# PushButton_RGB_w_Test.net
KiCad netlist of a schematic drawn in EAGLE
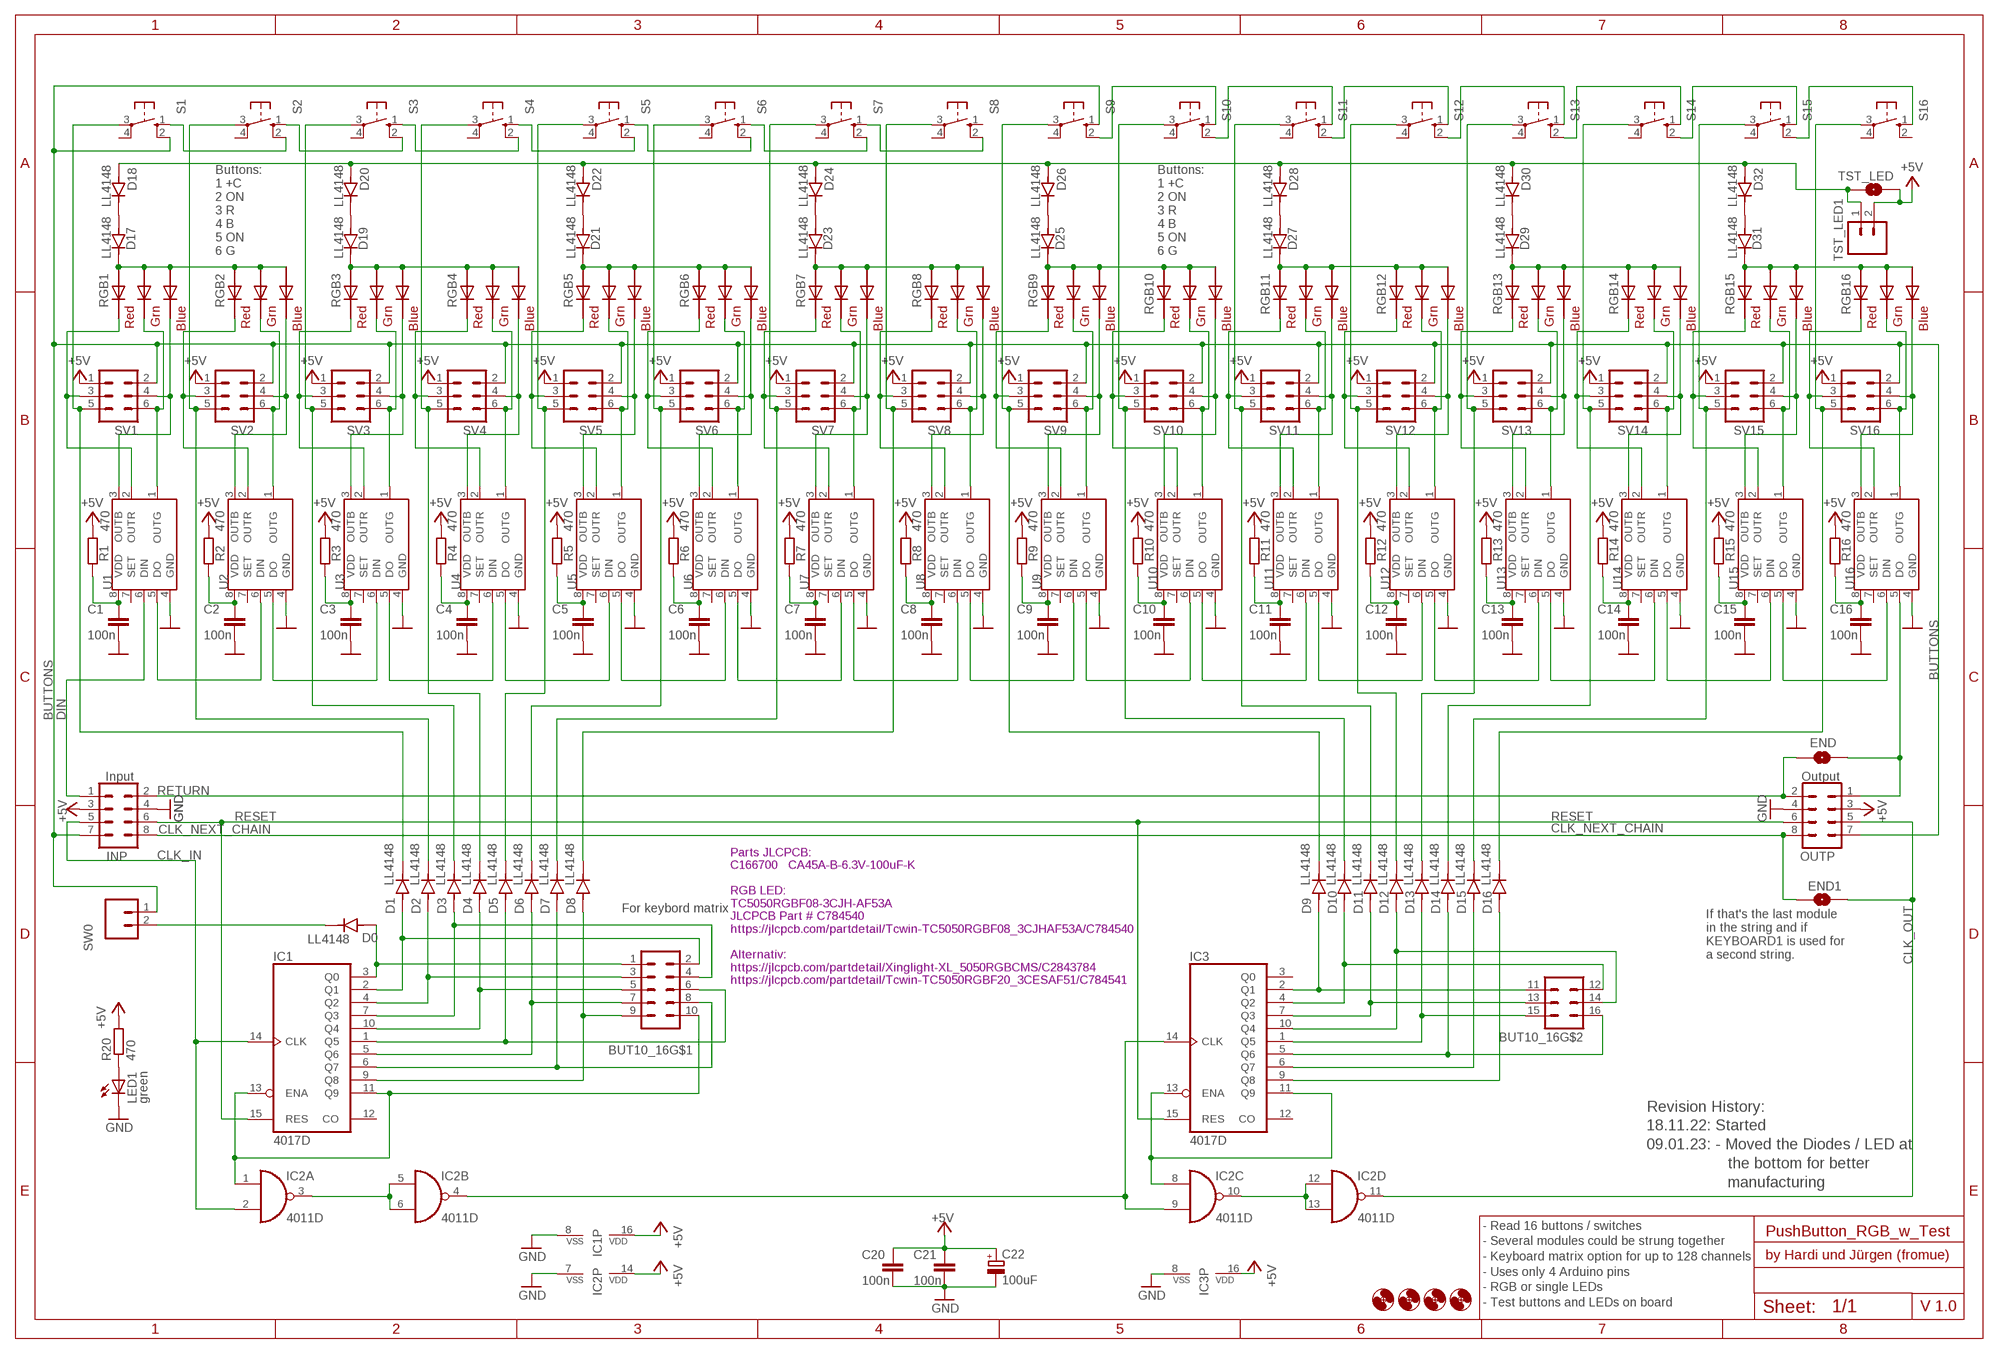
[diagram p0: schematic, sheet 1]

(export (version "E")
  (design (tool "Eeschema 10.0.6"))
  (components
    (comp (ref "BUT10_16")
      (value "CON-HARTING-ML_ML16-2")
      (footprint "eagle-import:CON-HARTING-ML_ML16")
      (libsource (lib "eagle-import") (part "CON-HARTING-ML_ML16-2"))
    )
    (comp (ref "C1")
      (value "100n")
      (footprint "eagle-import:C0603")
      (libsource (lib "eagle-import") (part "C-EUC0603"))
    )
    (comp (ref "C2")
      (value "100n")
      (footprint "eagle-import:C0603")
      (libsource (lib "eagle-import") (part "C-EUC0603"))
    )
    (comp (ref "C3")
      (value "100n")
      (footprint "eagle-import:C0603")
      (libsource (lib "eagle-import") (part "C-EUC0603"))
    )
    (comp (ref "C4")
      (value "100n")
      (footprint "eagle-import:C0603")
      (libsource (lib "eagle-import") (part "C-EUC0603"))
    )
    (comp (ref "C5")
      (value "100n")
      (footprint "eagle-import:C0603")
      (libsource (lib "eagle-import") (part "C-EUC0603"))
    )
    (comp (ref "C6")
      (value "100n")
      (footprint "eagle-import:C0603")
      (libsource (lib "eagle-import") (part "C-EUC0603"))
    )
    (comp (ref "C7")
      (value "100n")
      (footprint "eagle-import:C0603")
      (libsource (lib "eagle-import") (part "C-EUC0603"))
    )
    (comp (ref "C8")
      (value "100n")
      (footprint "eagle-import:C0603")
      (libsource (lib "eagle-import") (part "C-EUC0603"))
    )
    (comp (ref "C9")
      (value "100n")
      (footprint "eagle-import:C0603")
      (libsource (lib "eagle-import") (part "C-EUC0603"))
    )
    (comp (ref "C10")
      (value "100n")
      (footprint "eagle-import:C0603")
      (libsource (lib "eagle-import") (part "C-EUC0603"))
    )
    (comp (ref "C11")
      (value "100n")
      (footprint "eagle-import:C0603")
      (libsource (lib "eagle-import") (part "C-EUC0603"))
    )
    (comp (ref "C12")
      (value "100n")
      (footprint "eagle-import:C0603")
      (libsource (lib "eagle-import") (part "C-EUC0603"))
    )
    (comp (ref "C13")
      (value "100n")
      (footprint "eagle-import:C0603")
      (libsource (lib "eagle-import") (part "C-EUC0603"))
    )
    (comp (ref "C14")
      (value "100n")
      (footprint "eagle-import:C0603")
      (libsource (lib "eagle-import") (part "C-EUC0603"))
    )
    (comp (ref "C15")
      (value "100n")
      (footprint "eagle-import:C0603")
      (libsource (lib "eagle-import") (part "C-EUC0603"))
    )
    (comp (ref "C16")
      (value "100n")
      (footprint "eagle-import:C0603")
      (libsource (lib "eagle-import") (part "C-EUC0603"))
    )
    (comp (ref "C20")
      (value "100n")
      (footprint "eagle-import:C0603")
      (libsource (lib "eagle-import") (part "C-EUC0603"))
    )
    (comp (ref "C21")
      (value "100n")
      (footprint "eagle-import:C0603")
      (libsource (lib "eagle-import") (part "C-EUC0603"))
    )
    (comp (ref "C22")
      (value "100uF")
      (footprint "eagle-import:B_3528-21R")
      (libsource (lib "eagle-import") (part "CPOL-EUB/3528-21R"))
    )
    (comp (ref "D0")
      (value "LL4148")
      (footprint "eagle-import:DIO_LL4148")
      (fields (field (name "MF") "ON"))
      (libsource (lib "eagle-import") (part "LL4148"))
    )
    (comp (ref "D1")
      (value "LL4148")
      (footprint "eagle-import:DIO_LL4148")
      (fields (field (name "MF") "ON"))
      (libsource (lib "eagle-import") (part "LL4148"))
    )
    (comp (ref "D2")
      (value "LL4148")
      (footprint "eagle-import:DIO_LL4148")
      (fields (field (name "MF") "ON"))
      (libsource (lib "eagle-import") (part "LL4148"))
    )
    (comp (ref "D3")
      (value "LL4148")
      (footprint "eagle-import:DIO_LL4148")
      (fields (field (name "MF") "ON"))
      (libsource (lib "eagle-import") (part "LL4148"))
    )
    (comp (ref "D4")
      (value "LL4148")
      (footprint "eagle-import:DIO_LL4148")
      (fields (field (name "MF") "ON"))
      (libsource (lib "eagle-import") (part "LL4148"))
    )
    (comp (ref "D5")
      (value "LL4148")
      (footprint "eagle-import:DIO_LL4148")
      (fields (field (name "MF") "ON"))
      (libsource (lib "eagle-import") (part "LL4148"))
    )
    (comp (ref "D6")
      (value "LL4148")
      (footprint "eagle-import:DIO_LL4148")
      (fields (field (name "MF") "ON"))
      (libsource (lib "eagle-import") (part "LL4148"))
    )
    (comp (ref "D7")
      (value "LL4148")
      (footprint "eagle-import:DIO_LL4148")
      (fields (field (name "MF") "ON"))
      (libsource (lib "eagle-import") (part "LL4148"))
    )
    (comp (ref "D8")
      (value "LL4148")
      (footprint "eagle-import:DIO_LL4148")
      (fields (field (name "MF") "ON"))
      (libsource (lib "eagle-import") (part "LL4148"))
    )
    (comp (ref "D9")
      (value "LL4148")
      (footprint "eagle-import:DIO_LL4148")
      (fields (field (name "MF") "ON"))
      (libsource (lib "eagle-import") (part "LL4148"))
    )
    (comp (ref "D10")
      (value "LL4148")
      (footprint "eagle-import:DIO_LL4148")
      (fields (field (name "MF") "ON"))
      (libsource (lib "eagle-import") (part "LL4148"))
    )
    (comp (ref "D11")
      (value "LL4148")
      (footprint "eagle-import:DIO_LL4148")
      (fields (field (name "MF") "ON"))
      (libsource (lib "eagle-import") (part "LL4148"))
    )
    (comp (ref "D12")
      (value "LL4148")
      (footprint "eagle-import:DIO_LL4148")
      (fields (field (name "MF") "ON"))
      (libsource (lib "eagle-import") (part "LL4148"))
    )
    (comp (ref "D13")
      (value "LL4148")
      (footprint "eagle-import:DIO_LL4148")
      (fields (field (name "MF") "ON"))
      (libsource (lib "eagle-import") (part "LL4148"))
    )
    (comp (ref "D14")
      (value "LL4148")
      (footprint "eagle-import:DIO_LL4148")
      (fields (field (name "MF") "ON"))
      (libsource (lib "eagle-import") (part "LL4148"))
    )
    (comp (ref "D15")
      (value "LL4148")
      (footprint "eagle-import:DIO_LL4148")
      (fields (field (name "MF") "ON"))
      (libsource (lib "eagle-import") (part "LL4148"))
    )
    (comp (ref "D16")
      (value "LL4148")
      (footprint "eagle-import:DIO_LL4148")
      (fields (field (name "MF") "ON"))
      (libsource (lib "eagle-import") (part "LL4148"))
    )
    (comp (ref "D17")
      (value "LL4148")
      (footprint "eagle-import:DIO_LL4148")
      (fields (field (name "MF") "ON"))
      (libsource (lib "eagle-import") (part "LL4148"))
    )
    (comp (ref "D18")
      (value "LL4148")
      (footprint "eagle-import:DIO_LL4148")
      (fields (field (name "MF") "ON"))
      (libsource (lib "eagle-import") (part "LL4148"))
    )
    (comp (ref "D19")
      (value "LL4148")
      (footprint "eagle-import:DIO_LL4148")
      (fields (field (name "MF") "ON"))
      (libsource (lib "eagle-import") (part "LL4148"))
    )
    (comp (ref "D20")
      (value "LL4148")
      (footprint "eagle-import:DIO_LL4148")
      (fields (field (name "MF") "ON"))
      (libsource (lib "eagle-import") (part "LL4148"))
    )
    (comp (ref "D21")
      (value "LL4148")
      (footprint "eagle-import:DIO_LL4148")
      (fields (field (name "MF") "ON"))
      (libsource (lib "eagle-import") (part "LL4148"))
    )
    (comp (ref "D22")
      (value "LL4148")
      (footprint "eagle-import:DIO_LL4148")
      (fields (field (name "MF") "ON"))
      (libsource (lib "eagle-import") (part "LL4148"))
    )
    (comp (ref "D23")
      (value "LL4148")
      (footprint "eagle-import:DIO_LL4148")
      (fields (field (name "MF") "ON"))
      (libsource (lib "eagle-import") (part "LL4148"))
    )
    (comp (ref "D24")
      (value "LL4148")
      (footprint "eagle-import:DIO_LL4148")
      (fields (field (name "MF") "ON"))
      (libsource (lib "eagle-import") (part "LL4148"))
    )
    (comp (ref "D25")
      (value "LL4148")
      (footprint "eagle-import:DIO_LL4148")
      (fields (field (name "MF") "ON"))
      (libsource (lib "eagle-import") (part "LL4148"))
    )
    (comp (ref "D26")
      (value "LL4148")
      (footprint "eagle-import:DIO_LL4148")
      (fields (field (name "MF") "ON"))
      (libsource (lib "eagle-import") (part "LL4148"))
    )
    (comp (ref "D27")
      (value "LL4148")
      (footprint "eagle-import:DIO_LL4148")
      (fields (field (name "MF") "ON"))
      (libsource (lib "eagle-import") (part "LL4148"))
    )
    (comp (ref "D28")
      (value "LL4148")
      (footprint "eagle-import:DIO_LL4148")
      (fields (field (name "MF") "ON"))
      (libsource (lib "eagle-import") (part "LL4148"))
    )
    (comp (ref "D29")
      (value "LL4148")
      (footprint "eagle-import:DIO_LL4148")
      (fields (field (name "MF") "ON"))
      (libsource (lib "eagle-import") (part "LL4148"))
    )
    (comp (ref "D30")
      (value "LL4148")
      (footprint "eagle-import:DIO_LL4148")
      (fields (field (name "MF") "ON"))
      (libsource (lib "eagle-import") (part "LL4148"))
    )
    (comp (ref "D31")
      (value "LL4148")
      (footprint "eagle-import:DIO_LL4148")
      (fields (field (name "MF") "ON"))
      (libsource (lib "eagle-import") (part "LL4148"))
    )
    (comp (ref "D32")
      (value "LL4148")
      (footprint "eagle-import:DIO_LL4148")
      (fields (field (name "MF") "ON"))
      (libsource (lib "eagle-import") (part "LL4148"))
    )
    (comp (ref "END")
      (value "SOLDERJUMPERNO")
      (footprint "eagle-import:SJ_2S-NO")
      (libsource (lib "eagle-import") (part "SOLDERJUMPERNO"))
    )
    (comp (ref "END1")
      (value "SOLDERJUMPERNO")
      (footprint "eagle-import:SJ_2S-NO")
      (libsource (lib "eagle-import") (part "SOLDERJUMPERNO"))
    )
    (comp (ref "H1")
      (value "MOUNT-HOLE3.0")
      (footprint "eagle-import:3,0")
      (libsource (lib "eagle-import") (part "MOUNT-HOLE3.0"))
    )
    (comp (ref "H2")
      (value "MOUNT-HOLE3.0")
      (footprint "eagle-import:3,0")
      (libsource (lib "eagle-import") (part "MOUNT-HOLE3.0"))
    )
    (comp (ref "H3")
      (value "MOUNT-HOLE3.0")
      (footprint "eagle-import:3,0")
      (libsource (lib "eagle-import") (part "MOUNT-HOLE3.0"))
    )
    (comp (ref "H4")
      (value "MOUNT-HOLE3.0")
      (footprint "eagle-import:3,0")
      (libsource (lib "eagle-import") (part "MOUNT-HOLE3.0"))
    )
    (comp (ref "IC1")
      (value "4017D")
      (footprint "eagle-import:SO16")
      (libsource (lib "eagle-import") (part "4017D"))
    )
    (comp (ref "IC2")
      (value "4011D")
      (footprint "eagle-import:SO14")
      (fields (field (name "SPICEPREFIX") "J"))
      (libsource (lib "eagle-import") (part "4011D"))
    )
    (comp (ref "IC3")
      (value "4017D")
      (footprint "eagle-import:SO16")
      (libsource (lib "eagle-import") (part "4017D"))
    )
    (comp (ref "INP")
      (value "CON-HARTING-ML_ML08")
      (footprint "eagle-import:CON-HARTING-ML_ML08")
      (libsource (lib "eagle-import") (part "CON-HARTING-ML_ML08"))
    )
    (comp (ref "LED1")
      (value "green")
      (footprint "eagle-import:CHIPLED_0805")
      (libsource (lib "eagle-import") (part "LEDCHIPLED_0805"))
    )
    (comp (ref "OUTP")
      (value "CON-HARTING-ML_ML08")
      (footprint "eagle-import:CON-HARTING-ML_ML08")
      (libsource (lib "eagle-import") (part "CON-HARTING-ML_ML08"))
    )
    (comp (ref "R1")
      (value "470")
      (footprint "eagle-import:R0603")
      (libsource (lib "eagle-import") (part "R-EU_R0603"))
    )
    (comp (ref "R2")
      (value "470")
      (footprint "eagle-import:R0603")
      (libsource (lib "eagle-import") (part "R-EU_R0603"))
    )
    (comp (ref "R3")
      (value "470")
      (footprint "eagle-import:R0603")
      (libsource (lib "eagle-import") (part "R-EU_R0603"))
    )
    (comp (ref "R4")
      (value "470")
      (footprint "eagle-import:R0603")
      (libsource (lib "eagle-import") (part "R-EU_R0603"))
    )
    (comp (ref "R5")
      (value "470")
      (footprint "eagle-import:R0603")
      (libsource (lib "eagle-import") (part "R-EU_R0603"))
    )
    (comp (ref "R6")
      (value "470")
      (footprint "eagle-import:R0603")
      (libsource (lib "eagle-import") (part "R-EU_R0603"))
    )
    (comp (ref "R7")
      (value "470")
      (footprint "eagle-import:R0603")
      (libsource (lib "eagle-import") (part "R-EU_R0603"))
    )
    (comp (ref "R8")
      (value "470")
      (footprint "eagle-import:R0603")
      (libsource (lib "eagle-import") (part "R-EU_R0603"))
    )
    (comp (ref "R9")
      (value "470")
      (footprint "eagle-import:R0603")
      (libsource (lib "eagle-import") (part "R-EU_R0603"))
    )
    (comp (ref "R10")
      (value "470")
      (footprint "eagle-import:R0603")
      (libsource (lib "eagle-import") (part "R-EU_R0603"))
    )
    (comp (ref "R11")
      (value "470")
      (footprint "eagle-import:R0603")
      (libsource (lib "eagle-import") (part "R-EU_R0603"))
    )
    (comp (ref "R12")
      (value "470")
      (footprint "eagle-import:R0603")
      (libsource (lib "eagle-import") (part "R-EU_R0603"))
    )
    (comp (ref "R13")
      (value "470")
      (footprint "eagle-import:R0603")
      (libsource (lib "eagle-import") (part "R-EU_R0603"))
    )
    (comp (ref "R14")
      (value "470")
      (footprint "eagle-import:R0603")
      (libsource (lib "eagle-import") (part "R-EU_R0603"))
    )
    (comp (ref "R15")
      (value "470")
      (footprint "eagle-import:R0603")
      (libsource (lib "eagle-import") (part "R-EU_R0603"))
    )
    (comp (ref "R16")
      (value "470")
      (footprint "eagle-import:R0603")
      (libsource (lib "eagle-import") (part "R-EU_R0603"))
    )
    (comp (ref "R20")
      (value "470")
      (footprint "eagle-import:R0603")
      (libsource (lib "eagle-import") (part "R-EU_R0603"))
    )
    (comp (ref "RGB1")
      (value "RGBLED5050")
      (footprint "eagle-import:RGBLED5050")
      (libsource (lib "eagle-import") (part "RGBLED5050"))
    )
    (comp (ref "RGB2")
      (value "RGBLED5050")
      (footprint "eagle-import:RGBLED5050")
      (libsource (lib "eagle-import") (part "RGBLED5050"))
    )
    (comp (ref "RGB3")
      (value "RGBLED5050")
      (footprint "eagle-import:RGBLED5050")
      (libsource (lib "eagle-import") (part "RGBLED5050"))
    )
    (comp (ref "RGB4")
      (value "RGBLED5050")
      (footprint "eagle-import:RGBLED5050")
      (libsource (lib "eagle-import") (part "RGBLED5050"))
    )
    (comp (ref "RGB5")
      (value "RGBLED5050")
      (footprint "eagle-import:RGBLED5050")
      (libsource (lib "eagle-import") (part "RGBLED5050"))
    )
    (comp (ref "RGB6")
      (value "RGBLED5050")
      (footprint "eagle-import:RGBLED5050")
      (libsource (lib "eagle-import") (part "RGBLED5050"))
    )
    (comp (ref "RGB7")
      (value "RGBLED5050")
      (footprint "eagle-import:RGBLED5050")
      (libsource (lib "eagle-import") (part "RGBLED5050"))
    )
    (comp (ref "RGB8")
      (value "RGBLED5050")
      (footprint "eagle-import:RGBLED5050")
      (libsource (lib "eagle-import") (part "RGBLED5050"))
    )
    (comp (ref "RGB9")
      (value "RGBLED5050")
      (footprint "eagle-import:RGBLED5050")
      (libsource (lib "eagle-import") (part "RGBLED5050"))
    )
    (comp (ref "RGB10")
      (value "RGBLED5050")
      (footprint "eagle-import:RGBLED5050")
      (libsource (lib "eagle-import") (part "RGBLED5050"))
    )
    (comp (ref "RGB11")
      (value "RGBLED5050")
      (footprint "eagle-import:RGBLED5050")
      (libsource (lib "eagle-import") (part "RGBLED5050"))
    )
    (comp (ref "RGB12")
      (value "RGBLED5050")
      (footprint "eagle-import:RGBLED5050")
      (libsource (lib "eagle-import") (part "RGBLED5050"))
    )
    (comp (ref "RGB13")
      (value "RGBLED5050")
      (footprint "eagle-import:RGBLED5050")
      (libsource (lib "eagle-import") (part "RGBLED5050"))
    )
    (comp (ref "RGB14")
      (value "RGBLED5050")
      (footprint "eagle-import:RGBLED5050")
      (libsource (lib "eagle-import") (part "RGBLED5050"))
    )
    (comp (ref "RGB15")
      (value "RGBLED5050")
      (footprint "eagle-import:RGBLED5050")
      (libsource (lib "eagle-import") (part "RGBLED5050"))
    )
    (comp (ref "RGB16")
      (value "RGBLED5050")
      (footprint "eagle-import:RGBLED5050")
      (libsource (lib "eagle-import") (part "RGBLED5050"))
    )
    (comp (ref "S1")
      (value "10-XXB3F-10XX_SMD")
      (footprint "eagle-import:B3F-10XX_SMD")
      (libsource (lib "eagle-import") (part "10-XXB3F-10XX_SMD"))
    )
    (comp (ref "S2")
      (value "10-XXB3F-10XX_SMD")
      (footprint "eagle-import:B3F-10XX_SMD")
      (libsource (lib "eagle-import") (part "10-XXB3F-10XX_SMD"))
    )
    (comp (ref "S3")
      (value "10-XXB3F-10XX_SMD")
      (footprint "eagle-import:B3F-10XX_SMD")
      (libsource (lib "eagle-import") (part "10-XXB3F-10XX_SMD"))
    )
    (comp (ref "S4")
      (value "10-XXB3F-10XX_SMD")
      (footprint "eagle-import:B3F-10XX_SMD")
      (libsource (lib "eagle-import") (part "10-XXB3F-10XX_SMD"))
    )
    (comp (ref "S5")
      (value "10-XXB3F-10XX_SMD")
      (footprint "eagle-import:B3F-10XX_SMD")
      (libsource (lib "eagle-import") (part "10-XXB3F-10XX_SMD"))
    )
    (comp (ref "S6")
      (value "10-XXB3F-10XX_SMD")
      (footprint "eagle-import:B3F-10XX_SMD")
      (libsource (lib "eagle-import") (part "10-XXB3F-10XX_SMD"))
    )
    (comp (ref "S7")
      (value "10-XXB3F-10XX_SMD")
      (footprint "eagle-import:B3F-10XX_SMD")
      (libsource (lib "eagle-import") (part "10-XXB3F-10XX_SMD"))
    )
    (comp (ref "S8")
      (value "10-XXB3F-10XX_SMD")
      (footprint "eagle-import:B3F-10XX_SMD")
      (libsource (lib "eagle-import") (part "10-XXB3F-10XX_SMD"))
    )
    (comp (ref "S9")
      (value "10-XXB3F-10XX_SMD")
      (footprint "eagle-import:B3F-10XX_SMD")
      (libsource (lib "eagle-import") (part "10-XXB3F-10XX_SMD"))
    )
    (comp (ref "S10")
      (value "10-XXB3F-10XX_SMD")
      (footprint "eagle-import:B3F-10XX_SMD")
      (libsource (lib "eagle-import") (part "10-XXB3F-10XX_SMD"))
    )
    (comp (ref "S11")
      (value "10-XXB3F-10XX_SMD")
      (footprint "eagle-import:B3F-10XX_SMD")
      (libsource (lib "eagle-import") (part "10-XXB3F-10XX_SMD"))
    )
    (comp (ref "S12")
      (value "10-XXB3F-10XX_SMD")
      (footprint "eagle-import:B3F-10XX_SMD")
      (libsource (lib "eagle-import") (part "10-XXB3F-10XX_SMD"))
    )
    (comp (ref "S13")
      (value "10-XXB3F-10XX_SMD")
      (footprint "eagle-import:B3F-10XX_SMD")
      (libsource (lib "eagle-import") (part "10-XXB3F-10XX_SMD"))
    )
    (comp (ref "S14")
      (value "10-XXB3F-10XX_SMD")
      (footprint "eagle-import:B3F-10XX_SMD")
      (libsource (lib "eagle-import") (part "10-XXB3F-10XX_SMD"))
    )
    (comp (ref "S15")
      (value "10-XXB3F-10XX_SMD")
      (footprint "eagle-import:B3F-10XX_SMD")
      (libsource (lib "eagle-import") (part "10-XXB3F-10XX_SMD"))
    )
    (comp (ref "S16")
      (value "10-XXB3F-10XX_SMD")
      (footprint "eagle-import:B3F-10XX_SMD")
      (libsource (lib "eagle-import") (part "10-XXB3F-10XX_SMD"))
    )
    (comp (ref "SV1")
      (value "CON-HARTING-ML_ML6")
      (footprint "eagle-import:CON-HARTING-ML_ML6")
      (libsource (lib "eagle-import") (part "CON-HARTING-ML_ML6"))
    )
    (comp (ref "SV2")
      (value "CON-HARTING-ML_ML6")
      (footprint "eagle-import:CON-HARTING-ML_ML6")
      (libsource (lib "eagle-import") (part "CON-HARTING-ML_ML6"))
    )
    (comp (ref "SV3")
      (value "CON-HARTING-ML_ML6")
      (footprint "eagle-import:CON-HARTING-ML_ML6")
      (libsource (lib "eagle-import") (part "CON-HARTING-ML_ML6"))
    )
    (comp (ref "SV4")
      (value "CON-HARTING-ML_ML6")
      (footprint "eagle-import:CON-HARTING-ML_ML6")
      (libsource (lib "eagle-import") (part "CON-HARTING-ML_ML6"))
    )
    (comp (ref "SV5")
      (value "CON-HARTING-ML_ML6")
      (footprint "eagle-import:CON-HARTING-ML_ML6")
      (libsource (lib "eagle-import") (part "CON-HARTING-ML_ML6"))
    )
    (comp (ref "SV6")
      (value "CON-HARTING-ML_ML6")
      (footprint "eagle-import:CON-HARTING-ML_ML6")
      (libsource (lib "eagle-import") (part "CON-HARTING-ML_ML6"))
    )
    (comp (ref "SV7")
      (value "CON-HARTING-ML_ML6")
      (footprint "eagle-import:CON-HARTING-ML_ML6")
      (libsource (lib "eagle-import") (part "CON-HARTING-ML_ML6"))
    )
    (comp (ref "SV8")
      (value "CON-HARTING-ML_ML6")
      (footprint "eagle-import:CON-HARTING-ML_ML6")
      (libsource (lib "eagle-import") (part "CON-HARTING-ML_ML6"))
    )
    (comp (ref "SV9")
      (value "CON-HARTING-ML_ML6")
      (footprint "eagle-import:CON-HARTING-ML_ML6")
      (libsource (lib "eagle-import") (part "CON-HARTING-ML_ML6"))
    )
    (comp (ref "SV10")
      (value "CON-HARTING-ML_ML6")
      (footprint "eagle-import:CON-HARTING-ML_ML6")
      (libsource (lib "eagle-import") (part "CON-HARTING-ML_ML6"))
    )
    (comp (ref "SV11")
      (value "CON-HARTING-ML_ML6")
      (footprint "eagle-import:CON-HARTING-ML_ML6")
      (libsource (lib "eagle-import") (part "CON-HARTING-ML_ML6"))
    )
    (comp (ref "SV12")
      (value "CON-HARTING-ML_ML6")
      (footprint "eagle-import:CON-HARTING-ML_ML6")
      (libsource (lib "eagle-import") (part "CON-HARTING-ML_ML6"))
    )
    (comp (ref "SV13")
      (value "CON-HARTING-ML_ML6")
      (footprint "eagle-import:CON-HARTING-ML_ML6")
      (libsource (lib "eagle-import") (part "CON-HARTING-ML_ML6"))
    )
    (comp (ref "SV14")
      (value "CON-HARTING-ML_ML6")
      (footprint "eagle-import:CON-HARTING-ML_ML6")
      (libsource (lib "eagle-import") (part "CON-HARTING-ML_ML6"))
    )
    (comp (ref "SV15")
      (value "CON-HARTING-ML_ML6")
      (footprint "eagle-import:CON-HARTING-ML_ML6")
      (libsource (lib "eagle-import") (part "CON-HARTING-ML_ML6"))
    )
    (comp (ref "SV16")
      (value "CON-HARTING-ML_ML6")
      (footprint "eagle-import:CON-HARTING-ML_ML6")
      (libsource (lib "eagle-import") (part "CON-HARTING-ML_ML6"))
    )
    (comp (ref "SW0")
      (value "M02PTH")
      (footprint "eagle-import:1X02")
      (libsource (lib "eagle-import") (part "M02PTH"))
    )
    (comp (ref "TST_LED")
      (value "SOLDERJUMPERNO")
      (footprint "eagle-import:SJ_2S-NO")
      (libsource (lib "eagle-import") (part "SOLDERJUMPERNO"))
    )
    (comp (ref "TST_LED1")
      (value "Tst_LED")
      (footprint "eagle-import:1X02")
      (libsource (lib "eagle-import") (part "M02PTH"))
    )
    (comp (ref "U1")
      (value "S3PO_MODUL_WS2811_SOUND_MP3-TF-16P_WS2811_AND_ATTINY_WS2811-ICSOP8")
      (footprint "eagle-import:SOP8")
      (libsource (lib "eagle-import") (part "S3PO_MODUL_WS2811_SOUND_MP3-TF-16P_WS2811_AND_ATTINY_WS2811-ICSOP8"))
    )
    (comp (ref "U2")
      (value "S3PO_MODUL_WS2811_SOUND_MP3-TF-16P_WS2811_AND_ATTINY_WS2811-ICSOP8")
      (footprint "eagle-import:SOP8")
      (libsource (lib "eagle-import") (part "S3PO_MODUL_WS2811_SOUND_MP3-TF-16P_WS2811_AND_ATTINY_WS2811-ICSOP8"))
    )
    (comp (ref "U3")
      (value "S3PO_MODUL_WS2811_SOUND_MP3-TF-16P_WS2811_AND_ATTINY_WS2811-ICSOP8")
      (footprint "eagle-import:SOP8")
      (libsource (lib "eagle-import") (part "S3PO_MODUL_WS2811_SOUND_MP3-TF-16P_WS2811_AND_ATTINY_WS2811-ICSOP8"))
    )
    (comp (ref "U4")
      (value "S3PO_MODUL_WS2811_SOUND_MP3-TF-16P_WS2811_AND_ATTINY_WS2811-ICSOP8")
      (footprint "eagle-import:SOP8")
      (libsource (lib "eagle-import") (part "S3PO_MODUL_WS2811_SOUND_MP3-TF-16P_WS2811_AND_ATTINY_WS2811-ICSOP8"))
    )
    (comp (ref "U5")
      (value "S3PO_MODUL_WS2811_SOUND_MP3-TF-16P_WS2811_AND_ATTINY_WS2811-ICSOP8")
      (footprint "eagle-import:SOP8")
      (libsource (lib "eagle-import") (part "S3PO_MODUL_WS2811_SOUND_MP3-TF-16P_WS2811_AND_ATTINY_WS2811-ICSOP8"))
    )
    (comp (ref "U6")
      (value "S3PO_MODUL_WS2811_SOUND_MP3-TF-16P_WS2811_AND_ATTINY_WS2811-ICSOP8")
      (footprint "eagle-import:SOP8")
      (libsource (lib "eagle-import") (part "S3PO_MODUL_WS2811_SOUND_MP3-TF-16P_WS2811_AND_ATTINY_WS2811-ICSOP8"))
    )
    (comp (ref "U7")
      (value "S3PO_MODUL_WS2811_SOUND_MP3-TF-16P_WS2811_AND_ATTINY_WS2811-ICSOP8")
      (footprint "eagle-import:SOP8")
      (libsource (lib "eagle-import") (part "S3PO_MODUL_WS2811_SOUND_MP3-TF-16P_WS2811_AND_ATTINY_WS2811-ICSOP8"))
    )
    (comp (ref "U8")
      (value "S3PO_MODUL_WS2811_SOUND_MP3-TF-16P_WS2811_AND_ATTINY_WS2811-ICSOP8")
      (footprint "eagle-import:SOP8")
      (libsource (lib "eagle-import") (part "S3PO_MODUL_WS2811_SOUND_MP3-TF-16P_WS2811_AND_ATTINY_WS2811-ICSOP8"))
    )
    (comp (ref "U9")
      (value "S3PO_MODUL_WS2811_SOUND_MP3-TF-16P_WS2811_AND_ATTINY_WS2811-ICSOP8")
      (footprint "eagle-import:SOP8")
      (libsource (lib "eagle-import") (part "S3PO_MODUL_WS2811_SOUND_MP3-TF-16P_WS2811_AND_ATTINY_WS2811-ICSOP8"))
    )
    (comp (ref "U10")
      (value "S3PO_MODUL_WS2811_SOUND_MP3-TF-16P_WS2811_AND_ATTINY_WS2811-ICSOP8")
      (footprint "eagle-import:SOP8")
      (libsource (lib "eagle-import") (part "S3PO_MODUL_WS2811_SOUND_MP3-TF-16P_WS2811_AND_ATTINY_WS2811-ICSOP8"))
    )
    (comp (ref "U11")
      (value "S3PO_MODUL_WS2811_SOUND_MP3-TF-16P_WS2811_AND_ATTINY_WS2811-ICSOP8")
      (footprint "eagle-import:SOP8")
      (libsource (lib "eagle-import") (part "S3PO_MODUL_WS2811_SOUND_MP3-TF-16P_WS2811_AND_ATTINY_WS2811-ICSOP8"))
    )
    (comp (ref "U12")
      (value "S3PO_MODUL_WS2811_SOUND_MP3-TF-16P_WS2811_AND_ATTINY_WS2811-ICSOP8")
      (footprint "eagle-import:SOP8")
      (libsource (lib "eagle-import") (part "S3PO_MODUL_WS2811_SOUND_MP3-TF-16P_WS2811_AND_ATTINY_WS2811-ICSOP8"))
    )
    (comp (ref "U13")
      (value "S3PO_MODUL_WS2811_SOUND_MP3-TF-16P_WS2811_AND_ATTINY_WS2811-ICSOP8")
      (footprint "eagle-import:SOP8")
      (libsource (lib "eagle-import") (part "S3PO_MODUL_WS2811_SOUND_MP3-TF-16P_WS2811_AND_ATTINY_WS2811-ICSOP8"))
    )
    (comp (ref "U14")
      (value "S3PO_MODUL_WS2811_SOUND_MP3-TF-16P_WS2811_AND_ATTINY_WS2811-ICSOP8")
      (footprint "eagle-import:SOP8")
      (libsource (lib "eagle-import") (part "S3PO_MODUL_WS2811_SOUND_MP3-TF-16P_WS2811_AND_ATTINY_WS2811-ICSOP8"))
    )
    (comp (ref "U15")
      (value "S3PO_MODUL_WS2811_SOUND_MP3-TF-16P_WS2811_AND_ATTINY_WS2811-ICSOP8")
      (footprint "eagle-import:SOP8")
      (libsource (lib "eagle-import") (part "S3PO_MODUL_WS2811_SOUND_MP3-TF-16P_WS2811_AND_ATTINY_WS2811-ICSOP8"))
    )
    (comp (ref "U16")
      (value "S3PO_MODUL_WS2811_SOUND_MP3-TF-16P_WS2811_AND_ATTINY_WS2811-ICSOP8")
      (footprint "eagle-import:SOP8")
      (libsource (lib "eagle-import") (part "S3PO_MODUL_WS2811_SOUND_MP3-TF-16P_WS2811_AND_ATTINY_WS2811-ICSOP8"))
    )
  )
  (nets
    (net (code "1") (name "+5V") (class "Default")
      (node (ref "C20") (pin "1") (pinfunction "1_1") (pintype "passive"))
      (node (ref "C21") (pin "1") (pinfunction "1_1") (pintype "passive"))
      (node (ref "C22") (pin "+") (pinfunction "+_+") (pintype "passive"))
      (node (ref "IC1") (pin "16") (pinfunction "VDD_16") (pintype "power_in"))
      (node (ref "IC2") (pin "14") (pinfunction "VDD_14") (pintype "power_in"))
      (node (ref "IC3") (pin "16") (pinfunction "VDD_16") (pintype "power_in"))
      (node (ref "INP") (pin "3") (pinfunction "3_3") (pintype "passive"))
      (node (ref "OUTP") (pin "3") (pinfunction "3_3") (pintype "passive"))
      (node (ref "R1") (pin "2") (pinfunction "2_2") (pintype "passive"))
      (node (ref "R10") (pin "2") (pinfunction "2_2") (pintype "passive"))
      (node (ref "R11") (pin "2") (pinfunction "2_2") (pintype "passive"))
      (node (ref "R12") (pin "2") (pinfunction "2_2") (pintype "passive"))
      (node (ref "R13") (pin "2") (pinfunction "2_2") (pintype "passive"))
      (node (ref "R14") (pin "2") (pinfunction "2_2") (pintype "passive"))
      (node (ref "R15") (pin "2") (pinfunction "2_2") (pintype "passive"))
      (node (ref "R16") (pin "2") (pinfunction "2_2") (pintype "passive"))
      (node (ref "R2") (pin "2") (pinfunction "2_2") (pintype "passive"))
      (node (ref "R20") (pin "2") (pinfunction "2_2") (pintype "passive"))
      (node (ref "R3") (pin "2") (pinfunction "2_2") (pintype "passive"))
      (node (ref "R4") (pin "2") (pinfunction "2_2") (pintype "passive"))
      (node (ref "R5") (pin "2") (pinfunction "2_2") (pintype "passive"))
      (node (ref "R6") (pin "2") (pinfunction "2_2") (pintype "passive"))
      (node (ref "R7") (pin "2") (pinfunction "2_2") (pintype "passive"))
      (node (ref "R8") (pin "2") (pinfunction "2_2") (pintype "passive"))
      (node (ref "R9") (pin "2") (pinfunction "2_2") (pintype "passive"))
      (node (ref "SV1") (pin "1") (pinfunction "1_1") (pintype "passive"))
      (node (ref "SV10") (pin "1") (pinfunction "1_1") (pintype "passive"))
      (node (ref "SV11") (pin "1") (pinfunction "1_1") (pintype "passive"))
      (node (ref "SV12") (pin "1") (pinfunction "1_1") (pintype "passive"))
      (node (ref "SV13") (pin "1") (pinfunction "1_1") (pintype "passive"))
      (node (ref "SV14") (pin "1") (pinfunction "1_1") (pintype "passive"))
      (node (ref "SV15") (pin "1") (pinfunction "1_1") (pintype "passive"))
      (node (ref "SV16") (pin "1") (pinfunction "1_1") (pintype "passive"))
      (node (ref "SV2") (pin "1") (pinfunction "1_1") (pintype "passive"))
      (node (ref "SV3") (pin "1") (pinfunction "1_1") (pintype "passive"))
      (node (ref "SV4") (pin "1") (pinfunction "1_1") (pintype "passive"))
      (node (ref "SV5") (pin "1") (pinfunction "1_1") (pintype "passive"))
      (node (ref "SV6") (pin "1") (pinfunction "1_1") (pintype "passive"))
      (node (ref "SV7") (pin "1") (pinfunction "1_1") (pintype "passive"))
      (node (ref "SV8") (pin "1") (pinfunction "1_1") (pintype "passive"))
      (node (ref "SV9") (pin "1") (pinfunction "1_1") (pintype "passive"))
      (node (ref "TST_LED") (pin "1") (pinfunction "1_1") (pintype "passive"))
      (node (ref "TST_LED1") (pin "2") (pinfunction "2_2") (pintype "passive"))
    )
    (net (code "2") (name "/BUTTONS") (class "Default")
      (node (ref "INP") (pin "7") (pinfunction "7_7") (pintype "passive"))
      (node (ref "OUTP") (pin "7") (pinfunction "7_7") (pintype "passive"))
      (node (ref "S1") (pin "2") (pinfunction "S1_2") (pintype "passive"))
      (node (ref "S9") (pin "1") (pinfunction "S_1") (pintype "passive"))
      (node (ref "SV1") (pin "2") (pinfunction "2_2") (pintype "passive"))
      (node (ref "SV10") (pin "2") (pinfunction "2_2") (pintype "passive"))
      (node (ref "SV11") (pin "2") (pinfunction "2_2") (pintype "passive"))
      (node (ref "SV12") (pin "2") (pinfunction "2_2") (pintype "passive"))
      (node (ref "SV13") (pin "2") (pinfunction "2_2") (pintype "passive"))
      (node (ref "SV14") (pin "2") (pinfunction "2_2") (pintype "passive"))
      (node (ref "SV15") (pin "2") (pinfunction "2_2") (pintype "passive"))
      (node (ref "SV16") (pin "2") (pinfunction "2_2") (pintype "passive"))
      (node (ref "SV2") (pin "2") (pinfunction "2_2") (pintype "passive"))
      (node (ref "SV3") (pin "2") (pinfunction "2_2") (pintype "passive"))
      (node (ref "SV4") (pin "2") (pinfunction "2_2") (pintype "passive"))
      (node (ref "SV5") (pin "2") (pinfunction "2_2") (pintype "passive"))
      (node (ref "SV6") (pin "2") (pinfunction "2_2") (pintype "passive"))
      (node (ref "SV7") (pin "2") (pinfunction "2_2") (pintype "passive"))
      (node (ref "SV8") (pin "2") (pinfunction "2_2") (pintype "passive"))
      (node (ref "SV9") (pin "2") (pinfunction "2_2") (pintype "passive"))
      (node (ref "SW0") (pin "1") (pinfunction "1_1") (pintype "passive"))
    )
    (net (code "3") (name "/CLK_IN") (class "Default")
      (node (ref "IC1") (pin "14") (pinfunction "CLK_14") (pintype "input"))
      (node (ref "IC2") (pin "2") (pinfunction "I1_2") (pintype "input"))
      (node (ref "INP") (pin "5") (pinfunction "5_5") (pintype "passive"))
    )
    (net (code "4") (name "/CLK_NEXT_CHAIN") (class "Default")
      (node (ref "END1") (pin "2") (pinfunction "2_2") (pintype "passive"))
      (node (ref "INP") (pin "8") (pinfunction "8_8") (pintype "passive"))
      (node (ref "OUTP") (pin "8") (pinfunction "8_8") (pintype "passive"))
    )
    (net (code "5") (name "/CLK_OUT") (class "Default")
      (node (ref "END1") (pin "1") (pinfunction "1_1") (pintype "passive"))
      (node (ref "IC2") (pin "11") (pinfunction "O_11") (pintype "output"))
      (node (ref "OUTP") (pin "5") (pinfunction "5_5") (pintype "passive"))
    )
    (net (code "6") (name "/DIN") (class "Default")
      (node (ref "INP") (pin "1") (pinfunction "1_1") (pintype "passive"))
      (node (ref "U1") (pin "6") (pinfunction "DIN_6") (pintype "input"))
    )
    (net (code "7") (name "/RESET") (class "Default")
      (node (ref "IC1") (pin "15") (pinfunction "RES_15") (pintype "input"))
      (node (ref "IC3") (pin "15") (pinfunction "RES_15") (pintype "input"))
      (node (ref "INP") (pin "6") (pinfunction "6_6") (pintype "passive"))
      (node (ref "OUTP") (pin "6") (pinfunction "6_6") (pintype "passive"))
    )
    (net (code "8") (name "/RETURN") (class "Default")
      (node (ref "END") (pin "1") (pinfunction "1_1") (pintype "passive"))
      (node (ref "INP") (pin "2") (pinfunction "2_2") (pintype "passive"))
      (node (ref "OUTP") (pin "2") (pinfunction "2_2") (pintype "passive"))
    )
    (net (code "9") (name "GND") (class "Default")
      (node (ref "C1") (pin "2") (pinfunction "2_2") (pintype "passive"))
      (node (ref "C10") (pin "2") (pinfunction "2_2") (pintype "passive"))
      (node (ref "C11") (pin "2") (pinfunction "2_2") (pintype "passive"))
      (node (ref "C12") (pin "2") (pinfunction "2_2") (pintype "passive"))
      (node (ref "C13") (pin "2") (pinfunction "2_2") (pintype "passive"))
      (node (ref "C14") (pin "2") (pinfunction "2_2") (pintype "passive"))
      (node (ref "C15") (pin "2") (pinfunction "2_2") (pintype "passive"))
      (node (ref "C16") (pin "2") (pinfunction "2_2") (pintype "passive"))
      (node (ref "C2") (pin "2") (pinfunction "2_2") (pintype "passive"))
      (node (ref "C20") (pin "2") (pinfunction "2_2") (pintype "passive"))
      (node (ref "C21") (pin "2") (pinfunction "2_2") (pintype "passive"))
      (node (ref "C22") (pin "-") (pinfunction "-_-") (pintype "passive"))
      (node (ref "C3") (pin "2") (pinfunction "2_2") (pintype "passive"))
      (node (ref "C4") (pin "2") (pinfunction "2_2") (pintype "passive"))
      (node (ref "C5") (pin "2") (pinfunction "2_2") (pintype "passive"))
      (node (ref "C6") (pin "2") (pinfunction "2_2") (pintype "passive"))
      (node (ref "C7") (pin "2") (pinfunction "2_2") (pintype "passive"))
      (node (ref "C8") (pin "2") (pinfunction "2_2") (pintype "passive"))
      (node (ref "C9") (pin "2") (pinfunction "2_2") (pintype "passive"))
      (node (ref "IC1") (pin "8") (pinfunction "VSS_8") (pintype "power_in"))
      (node (ref "IC2") (pin "7") (pinfunction "VSS_7") (pintype "power_in"))
      (node (ref "IC3") (pin "8") (pinfunction "VSS_8") (pintype "power_in"))
      (node (ref "INP") (pin "4") (pinfunction "4_4") (pintype "passive"))
      (node (ref "LED1") (pin "C") (pinfunction "C_C") (pintype "passive"))
      (node (ref "OUTP") (pin "4") (pinfunction "4_4") (pintype "passive"))
      (node (ref "U1") (pin "4") (pinfunction "GND_4") (pintype "power_in"))
      (node (ref "U10") (pin "4") (pinfunction "GND_4") (pintype "power_in"))
      (node (ref "U11") (pin "4") (pinfunction "GND_4") (pintype "power_in"))
      (node (ref "U12") (pin "4") (pinfunction "GND_4") (pintype "power_in"))
      (node (ref "U13") (pin "4") (pinfunction "GND_4") (pintype "power_in"))
      (node (ref "U14") (pin "4") (pinfunction "GND_4") (pintype "power_in"))
      (node (ref "U15") (pin "4") (pinfunction "GND_4") (pintype "power_in"))
      (node (ref "U16") (pin "4") (pinfunction "GND_4") (pintype "power_in"))
      (node (ref "U2") (pin "4") (pinfunction "GND_4") (pintype "power_in"))
      (node (ref "U3") (pin "4") (pinfunction "GND_4") (pintype "power_in"))
      (node (ref "U4") (pin "4") (pinfunction "GND_4") (pintype "power_in"))
      (node (ref "U5") (pin "4") (pinfunction "GND_4") (pintype "power_in"))
      (node (ref "U6") (pin "4") (pinfunction "GND_4") (pintype "power_in"))
      (node (ref "U7") (pin "4") (pinfunction "GND_4") (pintype "power_in"))
      (node (ref "U8") (pin "4") (pinfunction "GND_4") (pintype "power_in"))
      (node (ref "U9") (pin "4") (pinfunction "GND_4") (pintype "power_in"))
    )
    (net (code "10") (name "Net-(BUT10_16B-1)") (class "Default")
      (node (ref "BUT10_16") (pin "11") (pinfunction "1_11") (pintype "passive"))
      (node (ref "D9") (pin "A") (pinfunction "A_A") (pintype "passive"))
      (node (ref "IC3") (pin "2") (pinfunction "Q1_2") (pintype "output"))
    )
    (net (code "11") (name "Net-(BUT10_16B-2)") (class "Default")
      (node (ref "BUT10_16") (pin "12") (pinfunction "2_12") (pintype "passive"))
      (node (ref "D10") (pin "A") (pinfunction "A_A") (pintype "passive"))
      (node (ref "IC3") (pin "4") (pinfunction "Q2_4") (pintype "output"))
    )
    (net (code "12") (name "Net-(BUT10_16B-3)") (class "Default")
      (node (ref "BUT10_16") (pin "13") (pinfunction "3_13") (pintype "passive"))
      (node (ref "D11") (pin "A") (pinfunction "A_A") (pintype "passive"))
      (node (ref "IC3") (pin "7") (pinfunction "Q3_7") (pintype "output"))
    )
    (net (code "13") (name "Net-(BUT10_16B-4)") (class "Default")
      (node (ref "BUT10_16") (pin "14") (pinfunction "4_14") (pintype "passive"))
      (node (ref "D12") (pin "A") (pinfunction "A_A") (pintype "passive"))
      (node (ref "IC3") (pin "10") (pinfunction "Q4_10") (pintype "output"))
    )
    (net (code "14") (name "Net-(BUT10_16B-5)") (class "Default")
      (node (ref "BUT10_16") (pin "15") (pinfunction "5_15") (pintype "passive"))
      (node (ref "D13") (pin "A") (pinfunction "A_A") (pintype "passive"))
      (node (ref "IC3") (pin "1") (pinfunction "Q5_1") (pintype "output"))
    )
    (net (code "15") (name "Net-(BUT10_16B-6)") (class "Default")
      (node (ref "BUT10_16") (pin "16") (pinfunction "6_16") (pintype "passive"))
      (node (ref "D14") (pin "A") (pinfunction "A_A") (pintype "passive"))
      (node (ref "IC3") (pin "5") (pinfunction "Q6_5") (pintype "output"))
    )
    (net (code "16") (name "Net-(D0-PadC)") (class "Default")
      (node (ref "D0") (pin "C") (pinfunction "C_C") (pintype "passive"))
      (node (ref "SW0") (pin "2") (pinfunction "2_2") (pintype "passive"))
    )
    (net (code "17") (name "Net-(D17-PadA)") (class "Default")
      (node (ref "D17") (pin "A") (pinfunction "A_A") (pintype "passive"))
      (node (ref "D18") (pin "C") (pinfunction "C_C") (pintype "passive"))
    )
    (net (code "18") (name "Net-(D18-PadA)") (class "Default")
      (node (ref "D18") (pin "A") (pinfunction "A_A") (pintype "passive"))
      (node (ref "D20") (pin "A") (pinfunction "A_A") (pintype "passive"))
      (node (ref "D22") (pin "A") (pinfunction "A_A") (pintype "passive"))
      (node (ref "D24") (pin "A") (pinfunction "A_A") (pintype "passive"))
      (node (ref "D26") (pin "A") (pinfunction "A_A") (pintype "passive"))
      (node (ref "D28") (pin "A") (pinfunction "A_A") (pintype "passive"))
      (node (ref "D30") (pin "A") (pinfunction "A_A") (pintype "passive"))
      (node (ref "D32") (pin "A") (pinfunction "A_A") (pintype "passive"))
      (node (ref "TST_LED") (pin "2") (pinfunction "2_2") (pintype "passive"))
      (node (ref "TST_LED1") (pin "1") (pinfunction "1_1") (pintype "passive"))
    )
    (net (code "19") (name "Net-(D19-PadA)") (class "Default")
      (node (ref "D19") (pin "A") (pinfunction "A_A") (pintype "passive"))
      (node (ref "D20") (pin "C") (pinfunction "C_C") (pintype "passive"))
    )
    (net (code "20") (name "Net-(D21-PadA)") (class "Default")
      (node (ref "D21") (pin "A") (pinfunction "A_A") (pintype "passive"))
      (node (ref "D22") (pin "C") (pinfunction "C_C") (pintype "passive"))
    )
    (net (code "21") (name "Net-(D23-PadA)") (class "Default")
      (node (ref "D23") (pin "A") (pinfunction "A_A") (pintype "passive"))
      (node (ref "D24") (pin "C") (pinfunction "C_C") (pintype "passive"))
    )
    (net (code "22") (name "Net-(D25-PadA)") (class "Default")
      (node (ref "D25") (pin "A") (pinfunction "A_A") (pintype "passive"))
      (node (ref "D26") (pin "C") (pinfunction "C_C") (pintype "passive"))
    )
    (net (code "23") (name "Net-(D27-PadA)") (class "Default")
      (node (ref "D27") (pin "A") (pinfunction "A_A") (pintype "passive"))
      (node (ref "D28") (pin "C") (pinfunction "C_C") (pintype "passive"))
    )
    (net (code "24") (name "Net-(D29-PadA)") (class "Default")
      (node (ref "D29") (pin "A") (pinfunction "A_A") (pintype "passive"))
      (node (ref "D30") (pin "C") (pinfunction "C_C") (pintype "passive"))
    )
    (net (code "25") (name "Net-(D31-PadA)") (class "Default")
      (node (ref "D31") (pin "A") (pinfunction "A_A") (pintype "passive"))
      (node (ref "D32") (pin "C") (pinfunction "C_C") (pintype "passive"))
    )
    (net (code "26") (name "Net-(IC1A-ENA)") (class "Default")
      (node (ref "BUT10_16") (pin "10") (pinfunction "10_10") (pintype "passive"))
      (node (ref "IC1") (pin "11") (pinfunction "Q9_11") (pintype "output"))
      (node (ref "IC1") (pin "13") (pinfunction "ENA_13") (pintype "input"))
      (node (ref "IC2") (pin "1") (pinfunction "I0_1") (pintype "input"))
    )
    (net (code "27") (name "Net-(IC1A-Q0)") (class "Default")
      (node (ref "BUT10_16") (pin "1") (pinfunction "1_1") (pintype "passive"))
      (node (ref "D0") (pin "A") (pinfunction "A_A") (pintype "passive"))
      (node (ref "IC1") (pin "3") (pinfunction "Q0_3") (pintype "output"))
    )
    (net (code "28") (name "Net-(IC1A-Q1)") (class "Default")
      (node (ref "BUT10_16") (pin "2") (pinfunction "2_2") (pintype "passive"))
      (node (ref "D1") (pin "A") (pinfunction "A_A") (pintype "passive"))
      (node (ref "IC1") (pin "2") (pinfunction "Q1_2") (pintype "output"))
    )
    (net (code "29") (name "Net-(IC1A-Q2)") (class "Default")
      (node (ref "BUT10_16") (pin "3") (pinfunction "3_3") (pintype "passive"))
      (node (ref "D2") (pin "A") (pinfunction "A_A") (pintype "passive"))
      (node (ref "IC1") (pin "4") (pinfunction "Q2_4") (pintype "output"))
    )
    (net (code "30") (name "Net-(IC1A-Q3)") (class "Default")
      (node (ref "BUT10_16") (pin "4") (pinfunction "4_4") (pintype "passive"))
      (node (ref "D3") (pin "A") (pinfunction "A_A") (pintype "passive"))
      (node (ref "IC1") (pin "7") (pinfunction "Q3_7") (pintype "output"))
    )
    (net (code "31") (name "Net-(IC1A-Q4)") (class "Default")
      (node (ref "BUT10_16") (pin "5") (pinfunction "5_5") (pintype "passive"))
      (node (ref "D4") (pin "A") (pinfunction "A_A") (pintype "passive"))
      (node (ref "IC1") (pin "10") (pinfunction "Q4_10") (pintype "output"))
    )
    (net (code "32") (name "Net-(IC1A-Q5)") (class "Default")
      (node (ref "BUT10_16") (pin "6") (pinfunction "6_6") (pintype "passive"))
      (node (ref "D5") (pin "A") (pinfunction "A_A") (pintype "passive"))
      (node (ref "IC1") (pin "1") (pinfunction "Q5_1") (pintype "output"))
    )
    (net (code "33") (name "Net-(IC1A-Q6)") (class "Default")
      (node (ref "BUT10_16") (pin "7") (pinfunction "7_7") (pintype "passive"))
      (node (ref "D6") (pin "A") (pinfunction "A_A") (pintype "passive"))
      (node (ref "IC1") (pin "5") (pinfunction "Q6_5") (pintype "output"))
    )
    (net (code "34") (name "Net-(IC1A-Q7)") (class "Default")
      (node (ref "BUT10_16") (pin "8") (pinfunction "8_8") (pintype "passive"))
      (node (ref "D7") (pin "A") (pinfunction "A_A") (pintype "passive"))
      (node (ref "IC1") (pin "6") (pinfunction "Q7_6") (pintype "output"))
    )
    (net (code "35") (name "Net-(IC1A-Q8)") (class "Default")
      (node (ref "BUT10_16") (pin "9") (pinfunction "9_9") (pintype "passive"))
      (node (ref "D8") (pin "A") (pinfunction "A_A") (pintype "passive"))
      (node (ref "IC1") (pin "9") (pinfunction "Q8_9") (pintype "output"))
    )
    (net (code "36") (name "Net-(IC2A-O)") (class "Default")
      (node (ref "IC2") (pin "3") (pinfunction "O_3") (pintype "output"))
      (node (ref "IC2") (pin "5") (pinfunction "I0_5") (pintype "input"))
      (node (ref "IC2") (pin "6") (pinfunction "I1_6") (pintype "input"))
    )
    (net (code "37") (name "Net-(IC2B-O)") (class "Default")
      (node (ref "IC2") (pin "4") (pinfunction "O_4") (pintype "output"))
      (node (ref "IC2") (pin "9") (pinfunction "I1_9") (pintype "input"))
      (node (ref "IC3") (pin "14") (pinfunction "CLK_14") (pintype "input"))
    )
    (net (code "38") (name "Net-(IC2C-I0)") (class "Default")
      (node (ref "IC2") (pin "8") (pinfunction "I0_8") (pintype "input"))
      (node (ref "IC3") (pin "11") (pinfunction "Q9_11") (pintype "output"))
      (node (ref "IC3") (pin "13") (pinfunction "ENA_13") (pintype "input"))
    )
    (net (code "39") (name "Net-(IC2C-O)") (class "Default")
      (node (ref "IC2") (pin "10") (pinfunction "O_10") (pintype "output"))
      (node (ref "IC2") (pin "12") (pinfunction "I0_12") (pintype "input"))
      (node (ref "IC2") (pin "13") (pinfunction "I1_13") (pintype "input"))
    )
    (net (code "40") (name "Net-(IC3A-Q7)") (class "Default")
      (node (ref "D15") (pin "A") (pinfunction "A_A") (pintype "passive"))
      (node (ref "IC3") (pin "6") (pinfunction "Q7_6") (pintype "output"))
    )
    (net (code "41") (name "Net-(IC3A-Q8)") (class "Default")
      (node (ref "D16") (pin "A") (pinfunction "A_A") (pintype "passive"))
      (node (ref "IC3") (pin "9") (pinfunction "Q8_9") (pintype "output"))
    )
    (net (code "42") (name "Net-(LED1-PadA)") (class "Default")
      (node (ref "LED1") (pin "A") (pinfunction "A_A") (pintype "passive"))
      (node (ref "R20") (pin "1") (pinfunction "1_1") (pintype "passive"))
    )
    (net (code "43") (name "Net-(RGB1-BLUE_A)") (class "Default")
      (node (ref "D17") (pin "C") (pinfunction "C_C") (pintype "passive"))
      (node (ref "RGB1") (pin "1") (pinfunction "GREEN_A_1") (pintype "bidirectional"))
      (node (ref "RGB1") (pin "2") (pinfunction "RED_A_2") (pintype "bidirectional"))
      (node (ref "RGB1") (pin "3") (pinfunction "BLUE_A_3") (pintype "bidirectional"))
      (node (ref "RGB2") (pin "1") (pinfunction "GREEN_A_1") (pintype "bidirectional"))
      (node (ref "RGB2") (pin "2") (pinfunction "RED_A_2") (pintype "bidirectional"))
      (node (ref "RGB2") (pin "3") (pinfunction "BLUE_A_3") (pintype "bidirectional"))
    )
    (net (code "44") (name "Net-(RGB1-BLUE_C)") (class "Default")
      (node (ref "RGB1") (pin "4") (pinfunction "BLUE_C_4") (pintype "bidirectional"))
      (node (ref "SV1") (pin "4") (pinfunction "4_4") (pintype "passive"))
      (node (ref "U1") (pin "3") (pinfunction "OUTB_3") (pintype "open_collector"))
    )
    (net (code "45") (name "Net-(RGB1-GREEN_C)") (class "Default")
      (node (ref "RGB1") (pin "6") (pinfunction "GREEN_C_6") (pintype "bidirectional"))
      (node (ref "SV1") (pin "6") (pinfunction "6_6") (pintype "passive"))
      (node (ref "U1") (pin "1") (pinfunction "OUTG_1") (pintype "open_collector"))
    )
    (net (code "46") (name "Net-(RGB1-RED_C)") (class "Default")
      (node (ref "RGB1") (pin "5") (pinfunction "RED_C_5") (pintype "bidirectional"))
      (node (ref "SV1") (pin "3") (pinfunction "3_3") (pintype "passive"))
      (node (ref "U1") (pin "2") (pinfunction "OUTR_2") (pintype "open_collector"))
    )
    (net (code "47") (name "Net-(RGB2-BLUE_C)") (class "Default")
      (node (ref "RGB2") (pin "4") (pinfunction "BLUE_C_4") (pintype "bidirectional"))
      (node (ref "SV2") (pin "4") (pinfunction "4_4") (pintype "passive"))
      (node (ref "U2") (pin "3") (pinfunction "OUTB_3") (pintype "open_collector"))
    )
    (net (code "48") (name "Net-(RGB2-GREEN_C)") (class "Default")
      (node (ref "RGB2") (pin "6") (pinfunction "GREEN_C_6") (pintype "bidirectional"))
      (node (ref "SV2") (pin "6") (pinfunction "6_6") (pintype "passive"))
      (node (ref "U2") (pin "1") (pinfunction "OUTG_1") (pintype "open_collector"))
    )
    (net (code "49") (name "Net-(RGB2-RED_C)") (class "Default")
      (node (ref "RGB2") (pin "5") (pinfunction "RED_C_5") (pintype "bidirectional"))
      (node (ref "SV2") (pin "3") (pinfunction "3_3") (pintype "passive"))
      (node (ref "U2") (pin "2") (pinfunction "OUTR_2") (pintype "open_collector"))
    )
    (net (code "50") (name "Net-(RGB3-BLUE_A)") (class "Default")
      (node (ref "D19") (pin "C") (pinfunction "C_C") (pintype "passive"))
      (node (ref "RGB3") (pin "1") (pinfunction "GREEN_A_1") (pintype "bidirectional"))
      (node (ref "RGB3") (pin "2") (pinfunction "RED_A_2") (pintype "bidirectional"))
      (node (ref "RGB3") (pin "3") (pinfunction "BLUE_A_3") (pintype "bidirectional"))
      (node (ref "RGB4") (pin "1") (pinfunction "GREEN_A_1") (pintype "bidirectional"))
      (node (ref "RGB4") (pin "2") (pinfunction "RED_A_2") (pintype "bidirectional"))
      (node (ref "RGB4") (pin "3") (pinfunction "BLUE_A_3") (pintype "bidirectional"))
    )
    (net (code "51") (name "Net-(RGB3-BLUE_C)") (class "Default")
      (node (ref "RGB3") (pin "4") (pinfunction "BLUE_C_4") (pintype "bidirectional"))
      (node (ref "SV3") (pin "4") (pinfunction "4_4") (pintype "passive"))
      (node (ref "U3") (pin "3") (pinfunction "OUTB_3") (pintype "open_collector"))
    )
    (net (code "52") (name "Net-(RGB3-GREEN_C)") (class "Default")
      (node (ref "RGB3") (pin "6") (pinfunction "GREEN_C_6") (pintype "bidirectional"))
      (node (ref "SV3") (pin "6") (pinfunction "6_6") (pintype "passive"))
      (node (ref "U3") (pin "1") (pinfunction "OUTG_1") (pintype "open_collector"))
    )
    (net (code "53") (name "Net-(RGB3-RED_C)") (class "Default")
      (node (ref "RGB3") (pin "5") (pinfunction "RED_C_5") (pintype "bidirectional"))
      (node (ref "SV3") (pin "3") (pinfunction "3_3") (pintype "passive"))
      (node (ref "U3") (pin "2") (pinfunction "OUTR_2") (pintype "open_collector"))
    )
    (net (code "54") (name "Net-(RGB4-BLUE_C)") (class "Default")
      (node (ref "RGB4") (pin "4") (pinfunction "BLUE_C_4") (pintype "bidirectional"))
      (node (ref "SV4") (pin "4") (pinfunction "4_4") (pintype "passive"))
      (node (ref "U4") (pin "3") (pinfunction "OUTB_3") (pintype "open_collector"))
    )
    (net (code "55") (name "Net-(RGB4-GREEN_C)") (class "Default")
      (node (ref "RGB4") (pin "6") (pinfunction "GREEN_C_6") (pintype "bidirectional"))
      (node (ref "SV4") (pin "6") (pinfunction "6_6") (pintype "passive"))
      (node (ref "U4") (pin "1") (pinfunction "OUTG_1") (pintype "open_collector"))
    )
    (net (code "56") (name "Net-(RGB4-RED_C)") (class "Default")
      (node (ref "RGB4") (pin "5") (pinfunction "RED_C_5") (pintype "bidirectional"))
      (node (ref "SV4") (pin "3") (pinfunction "3_3") (pintype "passive"))
      (node (ref "U4") (pin "2") (pinfunction "OUTR_2") (pintype "open_collector"))
    )
    (net (code "57") (name "Net-(RGB5-BLUE_A)") (class "Default")
      (node (ref "D21") (pin "C") (pinfunction "C_C") (pintype "passive"))
      (node (ref "RGB5") (pin "1") (pinfunction "GREEN_A_1") (pintype "bidirectional"))
      (node (ref "RGB5") (pin "2") (pinfunction "RED_A_2") (pintype "bidirectional"))
      (node (ref "RGB5") (pin "3") (pinfunction "BLUE_A_3") (pintype "bidirectional"))
      (node (ref "RGB6") (pin "1") (pinfunction "GREEN_A_1") (pintype "bidirectional"))
      (node (ref "RGB6") (pin "2") (pinfunction "RED_A_2") (pintype "bidirectional"))
      (node (ref "RGB6") (pin "3") (pinfunction "BLUE_A_3") (pintype "bidirectional"))
    )
    (net (code "58") (name "Net-(RGB5-BLUE_C)") (class "Default")
      (node (ref "RGB5") (pin "4") (pinfunction "BLUE_C_4") (pintype "bidirectional"))
      (node (ref "SV5") (pin "4") (pinfunction "4_4") (pintype "passive"))
      (node (ref "U5") (pin "3") (pinfunction "OUTB_3") (pintype "open_collector"))
    )
    (net (code "59") (name "Net-(RGB5-GREEN_C)") (class "Default")
      (node (ref "RGB5") (pin "6") (pinfunction "GREEN_C_6") (pintype "bidirectional"))
      (node (ref "SV5") (pin "6") (pinfunction "6_6") (pintype "passive"))
      (node (ref "U5") (pin "1") (pinfunction "OUTG_1") (pintype "open_collector"))
    )
    (net (code "60") (name "Net-(RGB5-RED_C)") (class "Default")
      (node (ref "RGB5") (pin "5") (pinfunction "RED_C_5") (pintype "bidirectional"))
      (node (ref "SV5") (pin "3") (pinfunction "3_3") (pintype "passive"))
      (node (ref "U5") (pin "2") (pinfunction "OUTR_2") (pintype "open_collector"))
    )
    (net (code "61") (name "Net-(RGB6-BLUE_C)") (class "Default")
      (node (ref "RGB6") (pin "4") (pinfunction "BLUE_C_4") (pintype "bidirectional"))
      (node (ref "SV6") (pin "4") (pinfunction "4_4") (pintype "passive"))
      (node (ref "U6") (pin "3") (pinfunction "OUTB_3") (pintype "open_collector"))
    )
    (net (code "62") (name "Net-(RGB6-GREEN_C)") (class "Default")
      (node (ref "RGB6") (pin "6") (pinfunction "GREEN_C_6") (pintype "bidirectional"))
      (node (ref "SV6") (pin "6") (pinfunction "6_6") (pintype "passive"))
      (node (ref "U6") (pin "1") (pinfunction "OUTG_1") (pintype "open_collector"))
    )
    (net (code "63") (name "Net-(RGB6-RED_C)") (class "Default")
      (node (ref "RGB6") (pin "5") (pinfunction "RED_C_5") (pintype "bidirectional"))
      (node (ref "SV6") (pin "3") (pinfunction "3_3") (pintype "passive"))
      (node (ref "U6") (pin "2") (pinfunction "OUTR_2") (pintype "open_collector"))
    )
    (net (code "64") (name "Net-(RGB7-BLUE_A)") (class "Default")
      (node (ref "D23") (pin "C") (pinfunction "C_C") (pintype "passive"))
      (node (ref "RGB7") (pin "1") (pinfunction "GREEN_A_1") (pintype "bidirectional"))
      (node (ref "RGB7") (pin "2") (pinfunction "RED_A_2") (pintype "bidirectional"))
      (node (ref "RGB7") (pin "3") (pinfunction "BLUE_A_3") (pintype "bidirectional"))
      (node (ref "RGB8") (pin "1") (pinfunction "GREEN_A_1") (pintype "bidirectional"))
      (node (ref "RGB8") (pin "2") (pinfunction "RED_A_2") (pintype "bidirectional"))
      (node (ref "RGB8") (pin "3") (pinfunction "BLUE_A_3") (pintype "bidirectional"))
    )
    (net (code "65") (name "Net-(RGB7-BLUE_C)") (class "Default")
      (node (ref "RGB7") (pin "4") (pinfunction "BLUE_C_4") (pintype "bidirectional"))
      (node (ref "SV7") (pin "4") (pinfunction "4_4") (pintype "passive"))
      (node (ref "U7") (pin "3") (pinfunction "OUTB_3") (pintype "open_collector"))
    )
    (net (code "66") (name "Net-(RGB7-GREEN_C)") (class "Default")
      (node (ref "RGB7") (pin "6") (pinfunction "GREEN_C_6") (pintype "bidirectional"))
      (node (ref "SV7") (pin "6") (pinfunction "6_6") (pintype "passive"))
      (node (ref "U7") (pin "1") (pinfunction "OUTG_1") (pintype "open_collector"))
    )
    (net (code "67") (name "Net-(RGB7-RED_C)") (class "Default")
      (node (ref "RGB7") (pin "5") (pinfunction "RED_C_5") (pintype "bidirectional"))
      (node (ref "SV7") (pin "3") (pinfunction "3_3") (pintype "passive"))
      (node (ref "U7") (pin "2") (pinfunction "OUTR_2") (pintype "open_collector"))
    )
    (net (code "68") (name "Net-(RGB8-BLUE_C)") (class "Default")
      (node (ref "RGB8") (pin "4") (pinfunction "BLUE_C_4") (pintype "bidirectional"))
      (node (ref "SV8") (pin "4") (pinfunction "4_4") (pintype "passive"))
      (node (ref "U8") (pin "3") (pinfunction "OUTB_3") (pintype "open_collector"))
    )
    (net (code "69") (name "Net-(RGB8-GREEN_C)") (class "Default")
      (node (ref "RGB8") (pin "6") (pinfunction "GREEN_C_6") (pintype "bidirectional"))
      (node (ref "SV8") (pin "6") (pinfunction "6_6") (pintype "passive"))
      (node (ref "U8") (pin "1") (pinfunction "OUTG_1") (pintype "open_collector"))
    )
    (net (code "70") (name "Net-(RGB8-RED_C)") (class "Default")
      (node (ref "RGB8") (pin "5") (pinfunction "RED_C_5") (pintype "bidirectional"))
      (node (ref "SV8") (pin "3") (pinfunction "3_3") (pintype "passive"))
      (node (ref "U8") (pin "2") (pinfunction "OUTR_2") (pintype "open_collector"))
    )
    (net (code "71") (name "Net-(RGB9-BLUE_C)") (class "Default")
      (node (ref "RGB9") (pin "4") (pinfunction "BLUE_C_4") (pintype "bidirectional"))
      (node (ref "SV9") (pin "4") (pinfunction "4_4") (pintype "passive"))
      (node (ref "U9") (pin "3") (pinfunction "OUTB_3") (pintype "open_collector"))
    )
    (net (code "72") (name "Net-(RGB9-GREEN_C)") (class "Default")
      (node (ref "RGB9") (pin "6") (pinfunction "GREEN_C_6") (pintype "bidirectional"))
      (node (ref "SV9") (pin "6") (pinfunction "6_6") (pintype "passive"))
      (node (ref "U9") (pin "1") (pinfunction "OUTG_1") (pintype "open_collector"))
    )
    (net (code "73") (name "Net-(RGB9-RED_C)") (class "Default")
      (node (ref "RGB9") (pin "5") (pinfunction "RED_C_5") (pintype "bidirectional"))
      (node (ref "SV9") (pin "3") (pinfunction "3_3") (pintype "passive"))
      (node (ref "U9") (pin "2") (pinfunction "OUTR_2") (pintype "open_collector"))
    )
    (net (code "74") (name "Net-(RGB10-BLUE_A)") (class "Default")
      (node (ref "D25") (pin "C") (pinfunction "C_C") (pintype "passive"))
      (node (ref "RGB10") (pin "1") (pinfunction "GREEN_A_1") (pintype "bidirectional"))
      (node (ref "RGB10") (pin "2") (pinfunction "RED_A_2") (pintype "bidirectional"))
      (node (ref "RGB10") (pin "3") (pinfunction "BLUE_A_3") (pintype "bidirectional"))
      (node (ref "RGB9") (pin "1") (pinfunction "GREEN_A_1") (pintype "bidirectional"))
      (node (ref "RGB9") (pin "2") (pinfunction "RED_A_2") (pintype "bidirectional"))
      (node (ref "RGB9") (pin "3") (pinfunction "BLUE_A_3") (pintype "bidirectional"))
    )
    (net (code "75") (name "Net-(RGB10-BLUE_C)") (class "Default")
      (node (ref "RGB10") (pin "4") (pinfunction "BLUE_C_4") (pintype "bidirectional"))
      (node (ref "SV10") (pin "4") (pinfunction "4_4") (pintype "passive"))
      (node (ref "U10") (pin "3") (pinfunction "OUTB_3") (pintype "open_collector"))
    )
    (net (code "76") (name "Net-(RGB10-GREEN_C)") (class "Default")
      (node (ref "RGB10") (pin "6") (pinfunction "GREEN_C_6") (pintype "bidirectional"))
      (node (ref "SV10") (pin "6") (pinfunction "6_6") (pintype "passive"))
      (node (ref "U10") (pin "1") (pinfunction "OUTG_1") (pintype "open_collector"))
    )
    (net (code "77") (name "Net-(RGB10-RED_C)") (class "Default")
      (node (ref "RGB10") (pin "5") (pinfunction "RED_C_5") (pintype "bidirectional"))
      (node (ref "SV10") (pin "3") (pinfunction "3_3") (pintype "passive"))
      (node (ref "U10") (pin "2") (pinfunction "OUTR_2") (pintype "open_collector"))
    )
    (net (code "78") (name "Net-(RGB11-BLUE_A)") (class "Default")
      (node (ref "D27") (pin "C") (pinfunction "C_C") (pintype "passive"))
      (node (ref "RGB11") (pin "1") (pinfunction "GREEN_A_1") (pintype "bidirectional"))
      (node (ref "RGB11") (pin "2") (pinfunction "RED_A_2") (pintype "bidirectional"))
      (node (ref "RGB11") (pin "3") (pinfunction "BLUE_A_3") (pintype "bidirectional"))
      (node (ref "RGB12") (pin "1") (pinfunction "GREEN_A_1") (pintype "bidirectional"))
      (node (ref "RGB12") (pin "2") (pinfunction "RED_A_2") (pintype "bidirectional"))
      (node (ref "RGB12") (pin "3") (pinfunction "BLUE_A_3") (pintype "bidirectional"))
    )
    (net (code "79") (name "Net-(RGB11-BLUE_C)") (class "Default")
      (node (ref "RGB11") (pin "4") (pinfunction "BLUE_C_4") (pintype "bidirectional"))
      (node (ref "SV11") (pin "4") (pinfunction "4_4") (pintype "passive"))
      (node (ref "U11") (pin "3") (pinfunction "OUTB_3") (pintype "open_collector"))
    )
    (net (code "80") (name "Net-(RGB11-GREEN_C)") (class "Default")
      (node (ref "RGB11") (pin "6") (pinfunction "GREEN_C_6") (pintype "bidirectional"))
      (node (ref "SV11") (pin "6") (pinfunction "6_6") (pintype "passive"))
      (node (ref "U11") (pin "1") (pinfunction "OUTG_1") (pintype "open_collector"))
    )
    (net (code "81") (name "Net-(RGB11-RED_C)") (class "Default")
      (node (ref "RGB11") (pin "5") (pinfunction "RED_C_5") (pintype "bidirectional"))
      (node (ref "SV11") (pin "3") (pinfunction "3_3") (pintype "passive"))
      (node (ref "U11") (pin "2") (pinfunction "OUTR_2") (pintype "open_collector"))
    )
    (net (code "82") (name "Net-(RGB12-BLUE_C)") (class "Default")
      (node (ref "RGB12") (pin "4") (pinfunction "BLUE_C_4") (pintype "bidirectional"))
      (node (ref "SV12") (pin "4") (pinfunction "4_4") (pintype "passive"))
      (node (ref "U12") (pin "3") (pinfunction "OUTB_3") (pintype "open_collector"))
    )
    (net (code "83") (name "Net-(RGB12-GREEN_C)") (class "Default")
      (node (ref "RGB12") (pin "6") (pinfunction "GREEN_C_6") (pintype "bidirectional"))
      (node (ref "SV12") (pin "6") (pinfunction "6_6") (pintype "passive"))
      (node (ref "U12") (pin "1") (pinfunction "OUTG_1") (pintype "open_collector"))
    )
    (net (code "84") (name "Net-(RGB12-RED_C)") (class "Default")
      (node (ref "RGB12") (pin "5") (pinfunction "RED_C_5") (pintype "bidirectional"))
      (node (ref "SV12") (pin "3") (pinfunction "3_3") (pintype "passive"))
      (node (ref "U12") (pin "2") (pinfunction "OUTR_2") (pintype "open_collector"))
    )
    (net (code "85") (name "Net-(RGB13-BLUE_A)") (class "Default")
      (node (ref "D29") (pin "C") (pinfunction "C_C") (pintype "passive"))
      (node (ref "RGB13") (pin "1") (pinfunction "GREEN_A_1") (pintype "bidirectional"))
      (node (ref "RGB13") (pin "2") (pinfunction "RED_A_2") (pintype "bidirectional"))
      (node (ref "RGB13") (pin "3") (pinfunction "BLUE_A_3") (pintype "bidirectional"))
      (node (ref "RGB14") (pin "1") (pinfunction "GREEN_A_1") (pintype "bidirectional"))
      (node (ref "RGB14") (pin "2") (pinfunction "RED_A_2") (pintype "bidirectional"))
      (node (ref "RGB14") (pin "3") (pinfunction "BLUE_A_3") (pintype "bidirectional"))
    )
    (net (code "86") (name "Net-(RGB13-BLUE_C)") (class "Default")
      (node (ref "RGB13") (pin "4") (pinfunction "BLUE_C_4") (pintype "bidirectional"))
      (node (ref "SV13") (pin "4") (pinfunction "4_4") (pintype "passive"))
      (node (ref "U13") (pin "3") (pinfunction "OUTB_3") (pintype "open_collector"))
    )
    (net (code "87") (name "Net-(RGB13-GREEN_C)") (class "Default")
      (node (ref "RGB13") (pin "6") (pinfunction "GREEN_C_6") (pintype "bidirectional"))
      (node (ref "SV13") (pin "6") (pinfunction "6_6") (pintype "passive"))
      (node (ref "U13") (pin "1") (pinfunction "OUTG_1") (pintype "open_collector"))
    )
    (net (code "88") (name "Net-(RGB13-RED_C)") (class "Default")
      (node (ref "RGB13") (pin "5") (pinfunction "RED_C_5") (pintype "bidirectional"))
      (node (ref "SV13") (pin "3") (pinfunction "3_3") (pintype "passive"))
      (node (ref "U13") (pin "2") (pinfunction "OUTR_2") (pintype "open_collector"))
    )
    (net (code "89") (name "Net-(RGB14-BLUE_C)") (class "Default")
      (node (ref "RGB14") (pin "4") (pinfunction "BLUE_C_4") (pintype "bidirectional"))
      (node (ref "SV14") (pin "4") (pinfunction "4_4") (pintype "passive"))
      (node (ref "U14") (pin "3") (pinfunction "OUTB_3") (pintype "open_collector"))
    )
    (net (code "90") (name "Net-(RGB14-GREEN_C)") (class "Default")
      (node (ref "RGB14") (pin "6") (pinfunction "GREEN_C_6") (pintype "bidirectional"))
      (node (ref "SV14") (pin "6") (pinfunction "6_6") (pintype "passive"))
      (node (ref "U14") (pin "1") (pinfunction "OUTG_1") (pintype "open_collector"))
    )
    (net (code "91") (name "Net-(RGB14-RED_C)") (class "Default")
      (node (ref "RGB14") (pin "5") (pinfunction "RED_C_5") (pintype "bidirectional"))
      (node (ref "SV14") (pin "3") (pinfunction "3_3") (pintype "passive"))
      (node (ref "U14") (pin "2") (pinfunction "OUTR_2") (pintype "open_collector"))
    )
    (net (code "92") (name "Net-(RGB15-BLUE_A)") (class "Default")
      (node (ref "D31") (pin "C") (pinfunction "C_C") (pintype "passive"))
      (node (ref "RGB15") (pin "1") (pinfunction "GREEN_A_1") (pintype "bidirectional"))
      (node (ref "RGB15") (pin "2") (pinfunction "RED_A_2") (pintype "bidirectional"))
      (node (ref "RGB15") (pin "3") (pinfunction "BLUE_A_3") (pintype "bidirectional"))
      (node (ref "RGB16") (pin "1") (pinfunction "GREEN_A_1") (pintype "bidirectional"))
      (node (ref "RGB16") (pin "2") (pinfunction "RED_A_2") (pintype "bidirectional"))
      (node (ref "RGB16") (pin "3") (pinfunction "BLUE_A_3") (pintype "bidirectional"))
    )
    (net (code "93") (name "Net-(RGB15-BLUE_C)") (class "Default")
      (node (ref "RGB15") (pin "4") (pinfunction "BLUE_C_4") (pintype "bidirectional"))
      (node (ref "SV15") (pin "4") (pinfunction "4_4") (pintype "passive"))
      (node (ref "U15") (pin "3") (pinfunction "OUTB_3") (pintype "open_collector"))
    )
    (net (code "94") (name "Net-(RGB15-GREEN_C)") (class "Default")
      (node (ref "RGB15") (pin "6") (pinfunction "GREEN_C_6") (pintype "bidirectional"))
      (node (ref "SV15") (pin "6") (pinfunction "6_6") (pintype "passive"))
      (node (ref "U15") (pin "1") (pinfunction "OUTG_1") (pintype "open_collector"))
    )
    (net (code "95") (name "Net-(RGB15-RED_C)") (class "Default")
      (node (ref "RGB15") (pin "5") (pinfunction "RED_C_5") (pintype "bidirectional"))
      (node (ref "SV15") (pin "3") (pinfunction "3_3") (pintype "passive"))
      (node (ref "U15") (pin "2") (pinfunction "OUTR_2") (pintype "open_collector"))
    )
    (net (code "96") (name "Net-(RGB16-BLUE_C)") (class "Default")
      (node (ref "RGB16") (pin "4") (pinfunction "BLUE_C_4") (pintype "bidirectional"))
      (node (ref "SV16") (pin "4") (pinfunction "4_4") (pintype "passive"))
      (node (ref "U16") (pin "3") (pinfunction "OUTB_3") (pintype "open_collector"))
    )
    (net (code "97") (name "Net-(RGB16-GREEN_C)") (class "Default")
      (node (ref "RGB16") (pin "6") (pinfunction "GREEN_C_6") (pintype "bidirectional"))
      (node (ref "SV16") (pin "6") (pinfunction "6_6") (pintype "passive"))
      (node (ref "U16") (pin "1") (pinfunction "OUTG_1") (pintype "open_collector"))
    )
    (net (code "98") (name "Net-(RGB16-RED_C)") (class "Default")
      (node (ref "RGB16") (pin "5") (pinfunction "RED_C_5") (pintype "bidirectional"))
      (node (ref "SV16") (pin "3") (pinfunction "3_3") (pintype "passive"))
      (node (ref "U16") (pin "2") (pinfunction "OUTR_2") (pintype "open_collector"))
    )
    (net (code "99") (name "Net-(S1-P)") (class "Default")
      (node (ref "D1") (pin "C") (pinfunction "C_C") (pintype "passive"))
      (node (ref "S1") (pin "3") (pinfunction "P_3") (pintype "passive"))
      (node (ref "SV1") (pin "5") (pinfunction "5_5") (pintype "passive"))
    )
    (net (code "100") (name "Net-(S1-S)") (class "Default")
      (node (ref "S1") (pin "1") (pinfunction "S_1") (pintype "passive"))
      (node (ref "S2") (pin "2") (pinfunction "S1_2") (pintype "passive"))
    )
    (net (code "101") (name "Net-(S2-P)") (class "Default")
      (node (ref "D2") (pin "C") (pinfunction "C_C") (pintype "passive"))
      (node (ref "S2") (pin "3") (pinfunction "P_3") (pintype "passive"))
      (node (ref "SV2") (pin "5") (pinfunction "5_5") (pintype "passive"))
    )
    (net (code "102") (name "Net-(S2-S)") (class "Default")
      (node (ref "S2") (pin "1") (pinfunction "S_1") (pintype "passive"))
      (node (ref "S3") (pin "2") (pinfunction "S1_2") (pintype "passive"))
    )
    (net (code "103") (name "Net-(S3-P)") (class "Default")
      (node (ref "D3") (pin "C") (pinfunction "C_C") (pintype "passive"))
      (node (ref "S3") (pin "3") (pinfunction "P_3") (pintype "passive"))
      (node (ref "SV3") (pin "5") (pinfunction "5_5") (pintype "passive"))
    )
    (net (code "104") (name "Net-(S3-S)") (class "Default")
      (node (ref "S3") (pin "1") (pinfunction "S_1") (pintype "passive"))
      (node (ref "S4") (pin "2") (pinfunction "S1_2") (pintype "passive"))
    )
    (net (code "105") (name "Net-(S4-P)") (class "Default")
      (node (ref "D4") (pin "C") (pinfunction "C_C") (pintype "passive"))
      (node (ref "S4") (pin "3") (pinfunction "P_3") (pintype "passive"))
      (node (ref "SV4") (pin "5") (pinfunction "5_5") (pintype "passive"))
    )
    (net (code "106") (name "Net-(S4-S)") (class "Default")
      (node (ref "S4") (pin "1") (pinfunction "S_1") (pintype "passive"))
      (node (ref "S5") (pin "2") (pinfunction "S1_2") (pintype "passive"))
    )
    (net (code "107") (name "Net-(S5-P)") (class "Default")
      (node (ref "D5") (pin "C") (pinfunction "C_C") (pintype "passive"))
      (node (ref "S5") (pin "3") (pinfunction "P_3") (pintype "passive"))
      (node (ref "SV5") (pin "5") (pinfunction "5_5") (pintype "passive"))
    )
    (net (code "108") (name "Net-(S5-S)") (class "Default")
      (node (ref "S5") (pin "1") (pinfunction "S_1") (pintype "passive"))
      (node (ref "S6") (pin "2") (pinfunction "S1_2") (pintype "passive"))
    )
    (net (code "109") (name "Net-(S6-P)") (class "Default")
      (node (ref "D6") (pin "C") (pinfunction "C_C") (pintype "passive"))
      (node (ref "S6") (pin "3") (pinfunction "P_3") (pintype "passive"))
      (node (ref "SV6") (pin "5") (pinfunction "5_5") (pintype "passive"))
    )
    (net (code "110") (name "Net-(S6-S)") (class "Default")
      (node (ref "S6") (pin "1") (pinfunction "S_1") (pintype "passive"))
      (node (ref "S7") (pin "2") (pinfunction "S1_2") (pintype "passive"))
    )
    (net (code "111") (name "Net-(S7-P)") (class "Default")
      (node (ref "D7") (pin "C") (pinfunction "C_C") (pintype "passive"))
      (node (ref "S7") (pin "3") (pinfunction "P_3") (pintype "passive"))
      (node (ref "SV7") (pin "5") (pinfunction "5_5") (pintype "passive"))
    )
    (net (code "112") (name "Net-(S7-S)") (class "Default")
      (node (ref "S7") (pin "1") (pinfunction "S_1") (pintype "passive"))
      (node (ref "S8") (pin "2") (pinfunction "S1_2") (pintype "passive"))
    )
    (net (code "113") (name "Net-(S8-P)") (class "Default")
      (node (ref "D8") (pin "C") (pinfunction "C_C") (pintype "passive"))
      (node (ref "S8") (pin "3") (pinfunction "P_3") (pintype "passive"))
      (node (ref "SV8") (pin "5") (pinfunction "5_5") (pintype "passive"))
    )
    (net (code "114") (name "Net-(S9-P)") (class "Default")
      (node (ref "D9") (pin "C") (pinfunction "C_C") (pintype "passive"))
      (node (ref "S9") (pin "3") (pinfunction "P_3") (pintype "passive"))
      (node (ref "SV9") (pin "5") (pinfunction "5_5") (pintype "passive"))
    )
    (net (code "115") (name "Net-(S10-P)") (class "Default")
      (node (ref "D10") (pin "C") (pinfunction "C_C") (pintype "passive"))
      (node (ref "S10") (pin "3") (pinfunction "P_3") (pintype "passive"))
      (node (ref "SV10") (pin "5") (pinfunction "5_5") (pintype "passive"))
    )
    (net (code "116") (name "Net-(S10-S)") (class "Default")
      (node (ref "S10") (pin "1") (pinfunction "S_1") (pintype "passive"))
      (node (ref "S9") (pin "2") (pinfunction "S1_2") (pintype "passive"))
    )
    (net (code "117") (name "Net-(S10-S1)") (class "Default")
      (node (ref "S10") (pin "2") (pinfunction "S1_2") (pintype "passive"))
      (node (ref "S11") (pin "1") (pinfunction "S_1") (pintype "passive"))
    )
    (net (code "118") (name "Net-(S11-P)") (class "Default")
      (node (ref "D11") (pin "C") (pinfunction "C_C") (pintype "passive"))
      (node (ref "S11") (pin "3") (pinfunction "P_3") (pintype "passive"))
      (node (ref "SV11") (pin "5") (pinfunction "5_5") (pintype "passive"))
    )
    (net (code "119") (name "Net-(S11-S1)") (class "Default")
      (node (ref "S11") (pin "2") (pinfunction "S1_2") (pintype "passive"))
      (node (ref "S12") (pin "1") (pinfunction "S_1") (pintype "passive"))
    )
    (net (code "120") (name "Net-(S12-P)") (class "Default")
      (node (ref "D12") (pin "C") (pinfunction "C_C") (pintype "passive"))
      (node (ref "S12") (pin "3") (pinfunction "P_3") (pintype "passive"))
      (node (ref "SV12") (pin "5") (pinfunction "5_5") (pintype "passive"))
    )
    (net (code "121") (name "Net-(S12-S1)") (class "Default")
      (node (ref "S12") (pin "2") (pinfunction "S1_2") (pintype "passive"))
      (node (ref "S13") (pin "1") (pinfunction "S_1") (pintype "passive"))
    )
    (net (code "122") (name "Net-(S13-P)") (class "Default")
      (node (ref "D13") (pin "C") (pinfunction "C_C") (pintype "passive"))
      (node (ref "S13") (pin "3") (pinfunction "P_3") (pintype "passive"))
      (node (ref "SV13") (pin "5") (pinfunction "5_5") (pintype "passive"))
    )
    (net (code "123") (name "Net-(S13-S1)") (class "Default")
      (node (ref "S13") (pin "2") (pinfunction "S1_2") (pintype "passive"))
      (node (ref "S14") (pin "1") (pinfunction "S_1") (pintype "passive"))
    )
    (net (code "124") (name "Net-(S14-P)") (class "Default")
      (node (ref "D14") (pin "C") (pinfunction "C_C") (pintype "passive"))
      (node (ref "S14") (pin "3") (pinfunction "P_3") (pintype "passive"))
      (node (ref "SV14") (pin "5") (pinfunction "5_5") (pintype "passive"))
    )
    (net (code "125") (name "Net-(S14-S1)") (class "Default")
      (node (ref "S14") (pin "2") (pinfunction "S1_2") (pintype "passive"))
      (node (ref "S15") (pin "1") (pinfunction "S_1") (pintype "passive"))
    )
    (net (code "126") (name "Net-(S15-P)") (class "Default")
      (node (ref "D15") (pin "C") (pinfunction "C_C") (pintype "passive"))
      (node (ref "S15") (pin "3") (pinfunction "P_3") (pintype "passive"))
      (node (ref "SV15") (pin "5") (pinfunction "5_5") (pintype "passive"))
    )
    (net (code "127") (name "Net-(S15-S1)") (class "Default")
      (node (ref "S15") (pin "2") (pinfunction "S1_2") (pintype "passive"))
      (node (ref "S16") (pin "1") (pinfunction "S_1") (pintype "passive"))
    )
    (net (code "128") (name "Net-(S16-P)") (class "Default")
      (node (ref "D16") (pin "C") (pinfunction "C_C") (pintype "passive"))
      (node (ref "S16") (pin "3") (pinfunction "P_3") (pintype "passive"))
      (node (ref "SV16") (pin "5") (pinfunction "5_5") (pintype "passive"))
    )
    (net (code "129") (name "Net-(U1-DO)") (class "Default")
      (node (ref "U1") (pin "5") (pinfunction "DO_5") (pintype "output"))
      (node (ref "U2") (pin "6") (pinfunction "DIN_6") (pintype "input"))
    )
    (net (code "130") (name "Net-(U1-VDD)") (class "Default")
      (node (ref "C1") (pin "1") (pinfunction "1_1") (pintype "passive"))
      (node (ref "R1") (pin "1") (pinfunction "1_1") (pintype "passive"))
      (node (ref "U1") (pin "8") (pinfunction "VDD_8") (pintype "power_in"))
    )
    (net (code "131") (name "Net-(U2-DO)") (class "Default")
      (node (ref "U2") (pin "5") (pinfunction "DO_5") (pintype "output"))
      (node (ref "U3") (pin "6") (pinfunction "DIN_6") (pintype "input"))
    )
    (net (code "132") (name "Net-(U2-VDD)") (class "Default")
      (node (ref "C2") (pin "1") (pinfunction "1_1") (pintype "passive"))
      (node (ref "R2") (pin "1") (pinfunction "1_1") (pintype "passive"))
      (node (ref "U2") (pin "8") (pinfunction "VDD_8") (pintype "power_in"))
    )
    (net (code "133") (name "Net-(U3-DO)") (class "Default")
      (node (ref "U3") (pin "5") (pinfunction "DO_5") (pintype "output"))
      (node (ref "U4") (pin "6") (pinfunction "DIN_6") (pintype "input"))
    )
    (net (code "134") (name "Net-(U3-VDD)") (class "Default")
      (node (ref "C3") (pin "1") (pinfunction "1_1") (pintype "passive"))
      (node (ref "R3") (pin "1") (pinfunction "1_1") (pintype "passive"))
      (node (ref "U3") (pin "8") (pinfunction "VDD_8") (pintype "power_in"))
    )
    (net (code "135") (name "Net-(U4-DO)") (class "Default")
      (node (ref "U4") (pin "5") (pinfunction "DO_5") (pintype "output"))
      (node (ref "U5") (pin "6") (pinfunction "DIN_6") (pintype "input"))
    )
    (net (code "136") (name "Net-(U4-VDD)") (class "Default")
      (node (ref "C4") (pin "1") (pinfunction "1_1") (pintype "passive"))
      (node (ref "R4") (pin "1") (pinfunction "1_1") (pintype "passive"))
      (node (ref "U4") (pin "8") (pinfunction "VDD_8") (pintype "power_in"))
    )
    (net (code "137") (name "Net-(U5-DO)") (class "Default")
      (node (ref "U5") (pin "5") (pinfunction "DO_5") (pintype "output"))
      (node (ref "U6") (pin "6") (pinfunction "DIN_6") (pintype "input"))
    )
    (net (code "138") (name "Net-(U5-VDD)") (class "Default")
      (node (ref "C5") (pin "1") (pinfunction "1_1") (pintype "passive"))
      (node (ref "R5") (pin "1") (pinfunction "1_1") (pintype "passive"))
      (node (ref "U5") (pin "8") (pinfunction "VDD_8") (pintype "power_in"))
    )
    (net (code "139") (name "Net-(U6-DO)") (class "Default")
      (node (ref "U6") (pin "5") (pinfunction "DO_5") (pintype "output"))
      (node (ref "U7") (pin "6") (pinfunction "DIN_6") (pintype "input"))
    )
    (net (code "140") (name "Net-(U6-VDD)") (class "Default")
      (node (ref "C6") (pin "1") (pinfunction "1_1") (pintype "passive"))
      (node (ref "R6") (pin "1") (pinfunction "1_1") (pintype "passive"))
      (node (ref "U6") (pin "8") (pinfunction "VDD_8") (pintype "power_in"))
    )
    (net (code "141") (name "Net-(U7-DO)") (class "Default")
      (node (ref "U7") (pin "5") (pinfunction "DO_5") (pintype "output"))
      (node (ref "U8") (pin "6") (pinfunction "DIN_6") (pintype "input"))
    )
    (net (code "142") (name "Net-(U7-VDD)") (class "Default")
      (node (ref "C7") (pin "1") (pinfunction "1_1") (pintype "passive"))
      (node (ref "R7") (pin "1") (pinfunction "1_1") (pintype "passive"))
      (node (ref "U7") (pin "8") (pinfunction "VDD_8") (pintype "power_in"))
    )
    (net (code "143") (name "Net-(U8-DO)") (class "Default")
      (node (ref "U8") (pin "5") (pinfunction "DO_5") (pintype "output"))
      (node (ref "U9") (pin "6") (pinfunction "DIN_6") (pintype "input"))
    )
    (net (code "144") (name "Net-(U8-VDD)") (class "Default")
      (node (ref "C8") (pin "1") (pinfunction "1_1") (pintype "passive"))
      (node (ref "R8") (pin "1") (pinfunction "1_1") (pintype "passive"))
      (node (ref "U8") (pin "8") (pinfunction "VDD_8") (pintype "power_in"))
    )
    (net (code "145") (name "Net-(U9-VDD)") (class "Default")
      (node (ref "C9") (pin "1") (pinfunction "1_1") (pintype "passive"))
      (node (ref "R9") (pin "1") (pinfunction "1_1") (pintype "passive"))
      (node (ref "U9") (pin "8") (pinfunction "VDD_8") (pintype "power_in"))
    )
    (net (code "146") (name "Net-(U10-DIN)") (class "Default")
      (node (ref "U10") (pin "6") (pinfunction "DIN_6") (pintype "input"))
      (node (ref "U9") (pin "5") (pinfunction "DO_5") (pintype "output"))
    )
    (net (code "147") (name "Net-(U10-DO)") (class "Default")
      (node (ref "U10") (pin "5") (pinfunction "DO_5") (pintype "output"))
      (node (ref "U11") (pin "6") (pinfunction "DIN_6") (pintype "input"))
    )
    (net (code "148") (name "Net-(U10-VDD)") (class "Default")
      (node (ref "C10") (pin "1") (pinfunction "1_1") (pintype "passive"))
      (node (ref "R10") (pin "1") (pinfunction "1_1") (pintype "passive"))
      (node (ref "U10") (pin "8") (pinfunction "VDD_8") (pintype "power_in"))
    )
    (net (code "149") (name "Net-(U11-DO)") (class "Default")
      (node (ref "U11") (pin "5") (pinfunction "DO_5") (pintype "output"))
      (node (ref "U12") (pin "6") (pinfunction "DIN_6") (pintype "input"))
    )
    (net (code "150") (name "Net-(U11-VDD)") (class "Default")
      (node (ref "C11") (pin "1") (pinfunction "1_1") (pintype "passive"))
      (node (ref "R11") (pin "1") (pinfunction "1_1") (pintype "passive"))
      (node (ref "U11") (pin "8") (pinfunction "VDD_8") (pintype "power_in"))
    )
    (net (code "151") (name "Net-(U12-DO)") (class "Default")
      (node (ref "U12") (pin "5") (pinfunction "DO_5") (pintype "output"))
      (node (ref "U13") (pin "6") (pinfunction "DIN_6") (pintype "input"))
    )
    (net (code "152") (name "Net-(U12-VDD)") (class "Default")
      (node (ref "C12") (pin "1") (pinfunction "1_1") (pintype "passive"))
      (node (ref "R12") (pin "1") (pinfunction "1_1") (pintype "passive"))
      (node (ref "U12") (pin "8") (pinfunction "VDD_8") (pintype "power_in"))
    )
    (net (code "153") (name "Net-(U13-DO)") (class "Default")
      (node (ref "U13") (pin "5") (pinfunction "DO_5") (pintype "output"))
      (node (ref "U14") (pin "6") (pinfunction "DIN_6") (pintype "input"))
    )
    (net (code "154") (name "Net-(U13-VDD)") (class "Default")
      (node (ref "C13") (pin "1") (pinfunction "1_1") (pintype "passive"))
      (node (ref "R13") (pin "1") (pinfunction "1_1") (pintype "passive"))
      (node (ref "U13") (pin "8") (pinfunction "VDD_8") (pintype "power_in"))
    )
    (net (code "155") (name "Net-(U14-DO)") (class "Default")
      (node (ref "U14") (pin "5") (pinfunction "DO_5") (pintype "output"))
      (node (ref "U15") (pin "6") (pinfunction "DIN_6") (pintype "input"))
    )
    (net (code "156") (name "Net-(U14-VDD)") (class "Default")
      (node (ref "C14") (pin "1") (pinfunction "1_1") (pintype "passive"))
      (node (ref "R14") (pin "1") (pinfunction "1_1") (pintype "passive"))
      (node (ref "U14") (pin "8") (pinfunction "VDD_8") (pintype "power_in"))
    )
    (net (code "157") (name "Net-(U15-DO)") (class "Default")
      (node (ref "U15") (pin "5") (pinfunction "DO_5") (pintype "output"))
      (node (ref "U16") (pin "6") (pinfunction "DIN_6") (pintype "input"))
    )
    (net (code "158") (name "Net-(U15-VDD)") (class "Default")
      (node (ref "C15") (pin "1") (pinfunction "1_1") (pintype "passive"))
      (node (ref "R15") (pin "1") (pinfunction "1_1") (pintype "passive"))
      (node (ref "U15") (pin "8") (pinfunction "VDD_8") (pintype "power_in"))
    )
    (net (code "159") (name "Net-(U16-DO)") (class "Default")
      (node (ref "END") (pin "2") (pinfunction "2_2") (pintype "passive"))
      (node (ref "OUTP") (pin "1") (pinfunction "1_1") (pintype "passive"))
      (node (ref "U16") (pin "5") (pinfunction "DO_5") (pintype "output"))
    )
    (net (code "160") (name "Net-(U16-VDD)") (class "Default")
      (node (ref "C16") (pin "1") (pinfunction "1_1") (pintype "passive"))
      (node (ref "R16") (pin "1") (pinfunction "1_1") (pintype "passive"))
      (node (ref "U16") (pin "8") (pinfunction "VDD_8") (pintype "power_in"))
    )
    (net (code "161") (name "unconnected-(IC1A-CO-Pad12)") (class "Default")
      (node (ref "IC1") (pin "12") (pinfunction "CO_12") (pintype "output"))
    )
    (net (code "162") (name "unconnected-(IC3A-CO-Pad12)") (class "Default")
      (node (ref "IC3") (pin "12") (pinfunction "CO_12") (pintype "output"))
    )
    (net (code "163") (name "unconnected-(IC3A-Q0-Pad3)") (class "Default")
      (node (ref "IC3") (pin "3") (pinfunction "Q0_3") (pintype "output"))
    )
    (net (code "164") (name "unconnected-(S1-P1-Pad4)") (class "Default")
      (node (ref "S1") (pin "4") (pinfunction "P1_4") (pintype "passive"))
    )
    (net (code "165") (name "unconnected-(S2-P1-Pad4)") (class "Default")
      (node (ref "S2") (pin "4") (pinfunction "P1_4") (pintype "passive"))
    )
    (net (code "166") (name "unconnected-(S3-P1-Pad4)") (class "Default")
      (node (ref "S3") (pin "4") (pinfunction "P1_4") (pintype "passive"))
    )
    (net (code "167") (name "unconnected-(S4-P1-Pad4)") (class "Default")
      (node (ref "S4") (pin "4") (pinfunction "P1_4") (pintype "passive"))
    )
    (net (code "168") (name "unconnected-(S5-P1-Pad4)") (class "Default")
      (node (ref "S5") (pin "4") (pinfunction "P1_4") (pintype "passive"))
    )
    (net (code "169") (name "unconnected-(S6-P1-Pad4)") (class "Default")
      (node (ref "S6") (pin "4") (pinfunction "P1_4") (pintype "passive"))
    )
    (net (code "170") (name "unconnected-(S7-P1-Pad4)") (class "Default")
      (node (ref "S7") (pin "4") (pinfunction "P1_4") (pintype "passive"))
    )
    (net (code "171") (name "unconnected-(S8-P1-Pad4)") (class "Default")
      (node (ref "S8") (pin "4") (pinfunction "P1_4") (pintype "passive"))
    )
    (net (code "172") (name "unconnected-(S8-S-Pad1)") (class "Default")
      (node (ref "S8") (pin "1") (pinfunction "S_1") (pintype "passive"))
    )
    (net (code "173") (name "unconnected-(S9-P1-Pad4)") (class "Default")
      (node (ref "S9") (pin "4") (pinfunction "P1_4") (pintype "passive"))
    )
    (net (code "174") (name "unconnected-(S10-P1-Pad4)") (class "Default")
      (node (ref "S10") (pin "4") (pinfunction "P1_4") (pintype "passive"))
    )
    (net (code "175") (name "unconnected-(S11-P1-Pad4)") (class "Default")
      (node (ref "S11") (pin "4") (pinfunction "P1_4") (pintype "passive"))
    )
    (net (code "176") (name "unconnected-(S12-P1-Pad4)") (class "Default")
      (node (ref "S12") (pin "4") (pinfunction "P1_4") (pintype "passive"))
    )
    (net (code "177") (name "unconnected-(S13-P1-Pad4)") (class "Default")
      (node (ref "S13") (pin "4") (pinfunction "P1_4") (pintype "passive"))
    )
    (net (code "178") (name "unconnected-(S14-P1-Pad4)") (class "Default")
      (node (ref "S14") (pin "4") (pinfunction "P1_4") (pintype "passive"))
    )
    (net (code "179") (name "unconnected-(S15-P1-Pad4)") (class "Default")
      (node (ref "S15") (pin "4") (pinfunction "P1_4") (pintype "passive"))
    )
    (net (code "180") (name "unconnected-(S16-P1-Pad4)") (class "Default")
      (node (ref "S16") (pin "4") (pinfunction "P1_4") (pintype "passive"))
    )
    (net (code "181") (name "unconnected-(S16-S1-Pad2)") (class "Default")
      (node (ref "S16") (pin "2") (pinfunction "S1_2") (pintype "passive"))
    )
    (net (code "182") (name "unconnected-(U1-SET-Pad7)") (class "Default")
      (node (ref "U1") (pin "7") (pinfunction "SET_7") (pintype "bidirectional"))
    )
    (net (code "183") (name "unconnected-(U2-SET-Pad7)") (class "Default")
      (node (ref "U2") (pin "7") (pinfunction "SET_7") (pintype "bidirectional"))
    )
    (net (code "184") (name "unconnected-(U3-SET-Pad7)") (class "Default")
      (node (ref "U3") (pin "7") (pinfunction "SET_7") (pintype "bidirectional"))
    )
    (net (code "185") (name "unconnected-(U4-SET-Pad7)") (class "Default")
      (node (ref "U4") (pin "7") (pinfunction "SET_7") (pintype "bidirectional"))
    )
    (net (code "186") (name "unconnected-(U5-SET-Pad7)") (class "Default")
      (node (ref "U5") (pin "7") (pinfunction "SET_7") (pintype "bidirectional"))
    )
    (net (code "187") (name "unconnected-(U6-SET-Pad7)") (class "Default")
      (node (ref "U6") (pin "7") (pinfunction "SET_7") (pintype "bidirectional"))
    )
    (net (code "188") (name "unconnected-(U7-SET-Pad7)") (class "Default")
      (node (ref "U7") (pin "7") (pinfunction "SET_7") (pintype "bidirectional"))
    )
    (net (code "189") (name "unconnected-(U8-SET-Pad7)") (class "Default")
      (node (ref "U8") (pin "7") (pinfunction "SET_7") (pintype "bidirectional"))
    )
    (net (code "190") (name "unconnected-(U9-SET-Pad7)") (class "Default")
      (node (ref "U9") (pin "7") (pinfunction "SET_7") (pintype "bidirectional"))
    )
    (net (code "191") (name "unconnected-(U10-SET-Pad7)") (class "Default")
      (node (ref "U10") (pin "7") (pinfunction "SET_7") (pintype "bidirectional"))
    )
    (net (code "192") (name "unconnected-(U11-SET-Pad7)") (class "Default")
      (node (ref "U11") (pin "7") (pinfunction "SET_7") (pintype "bidirectional"))
    )
    (net (code "193") (name "unconnected-(U12-SET-Pad7)") (class "Default")
      (node (ref "U12") (pin "7") (pinfunction "SET_7") (pintype "bidirectional"))
    )
    (net (code "194") (name "unconnected-(U13-SET-Pad7)") (class "Default")
      (node (ref "U13") (pin "7") (pinfunction "SET_7") (pintype "bidirectional"))
    )
    (net (code "195") (name "unconnected-(U14-SET-Pad7)") (class "Default")
      (node (ref "U14") (pin "7") (pinfunction "SET_7") (pintype "bidirectional"))
    )
    (net (code "196") (name "unconnected-(U15-SET-Pad7)") (class "Default")
      (node (ref "U15") (pin "7") (pinfunction "SET_7") (pintype "bidirectional"))
    )
    (net (code "197") (name "unconnected-(U16-SET-Pad7)") (class "Default")
      (node (ref "U16") (pin "7") (pinfunction "SET_7") (pintype "bidirectional"))
    )
  )
)
